# SMPS.net
KiCad netlist of a schematic drawn in Altium Designer
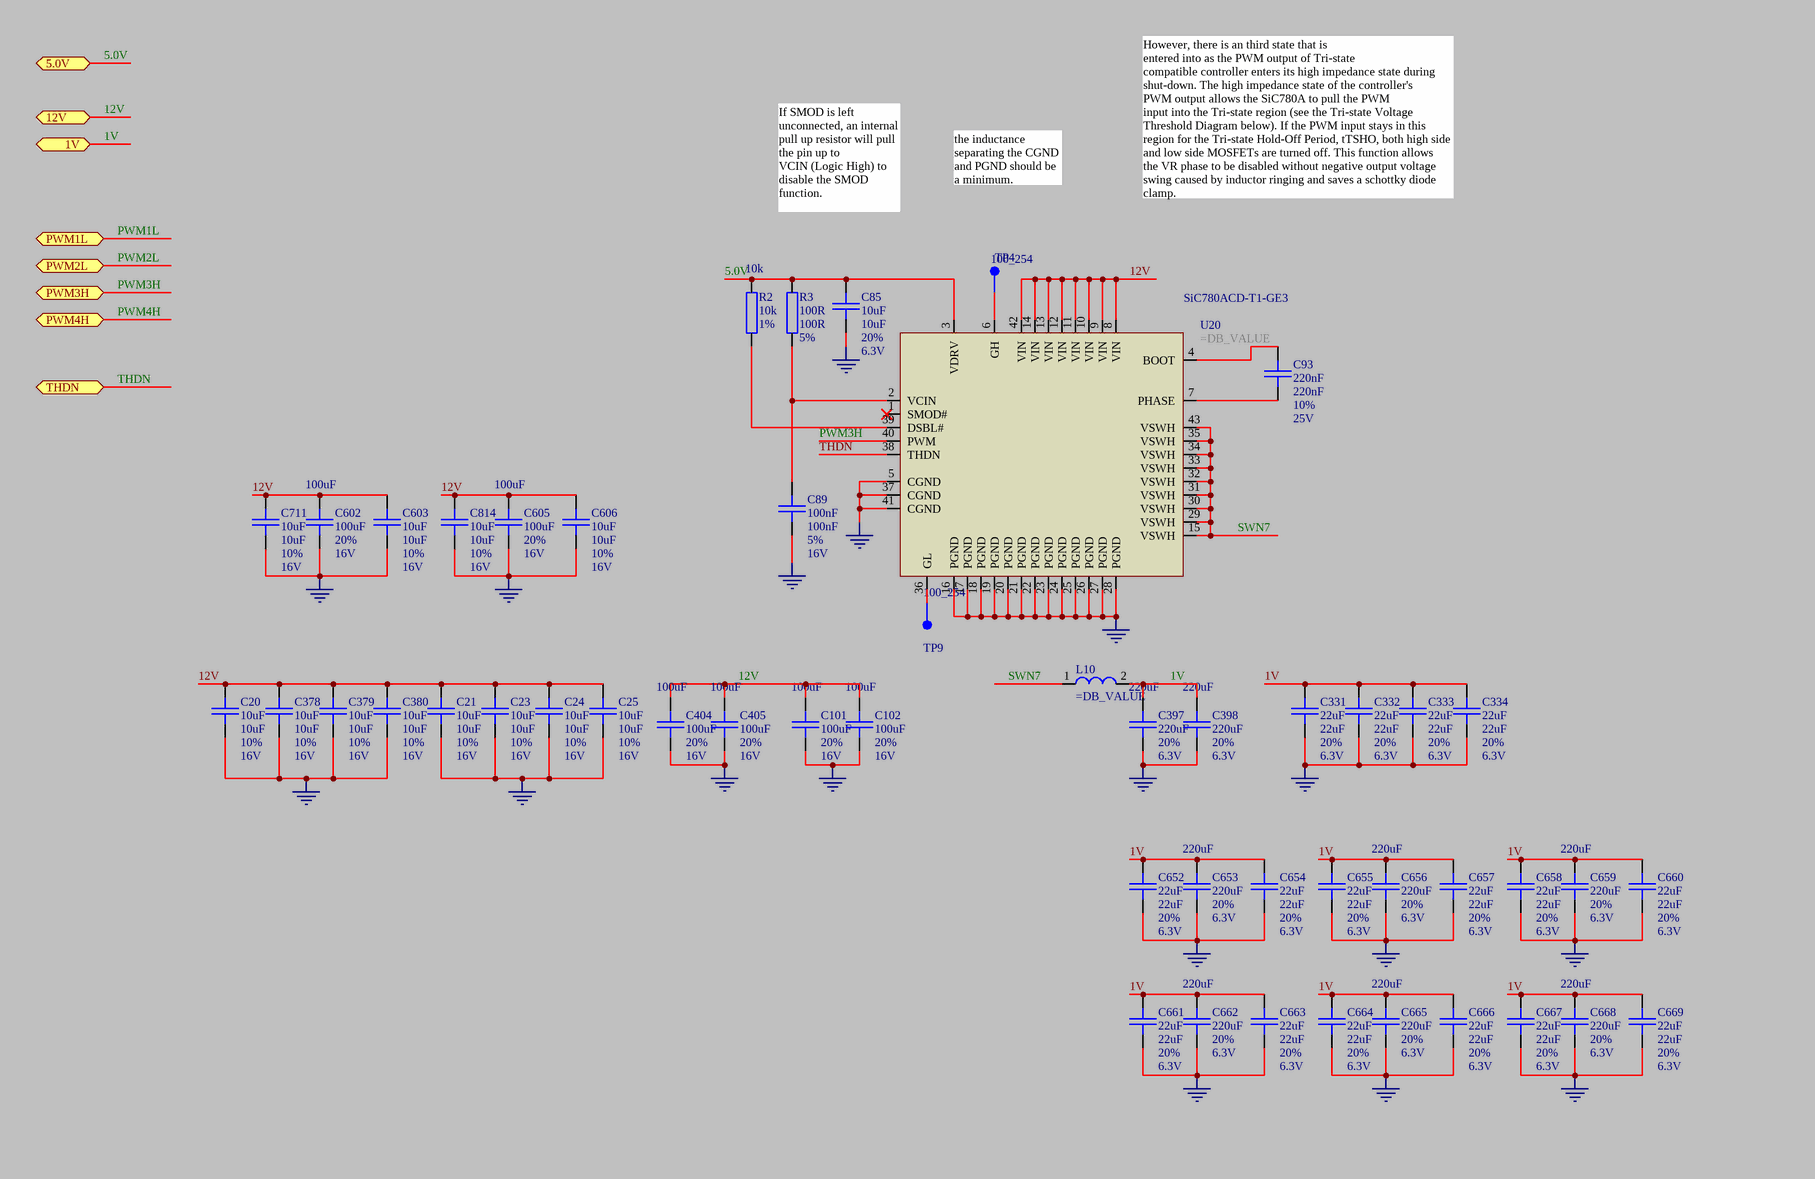
[diagram p0: SMPS.SchDoc, top left]
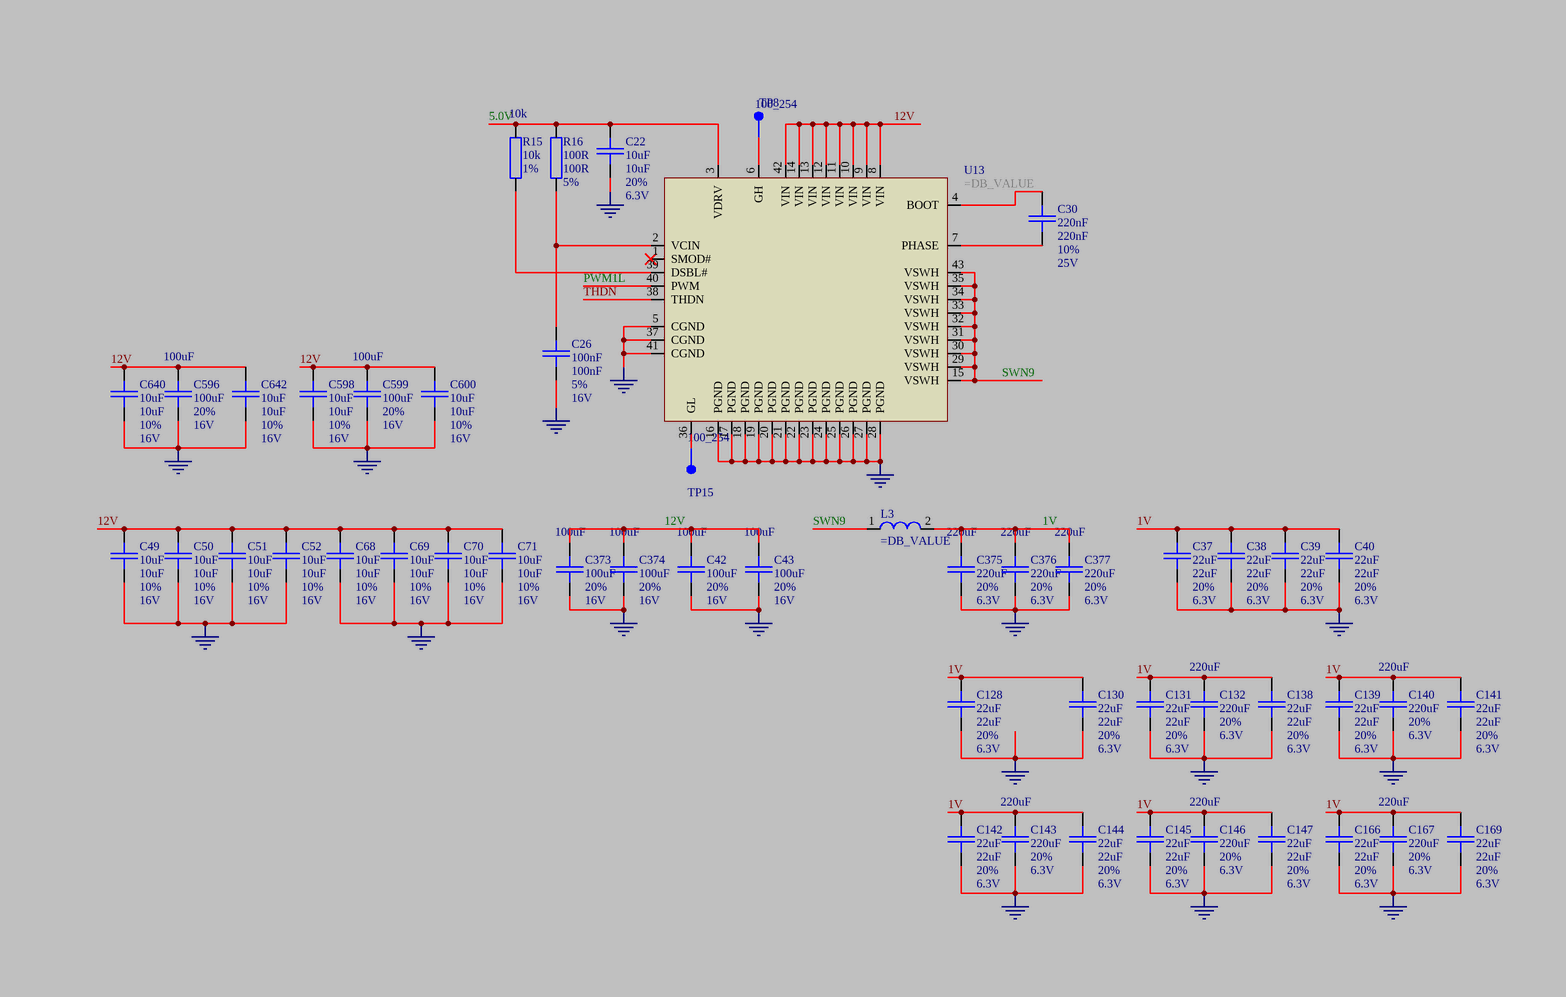
[diagram p1: SMPS.SchDoc, top right]
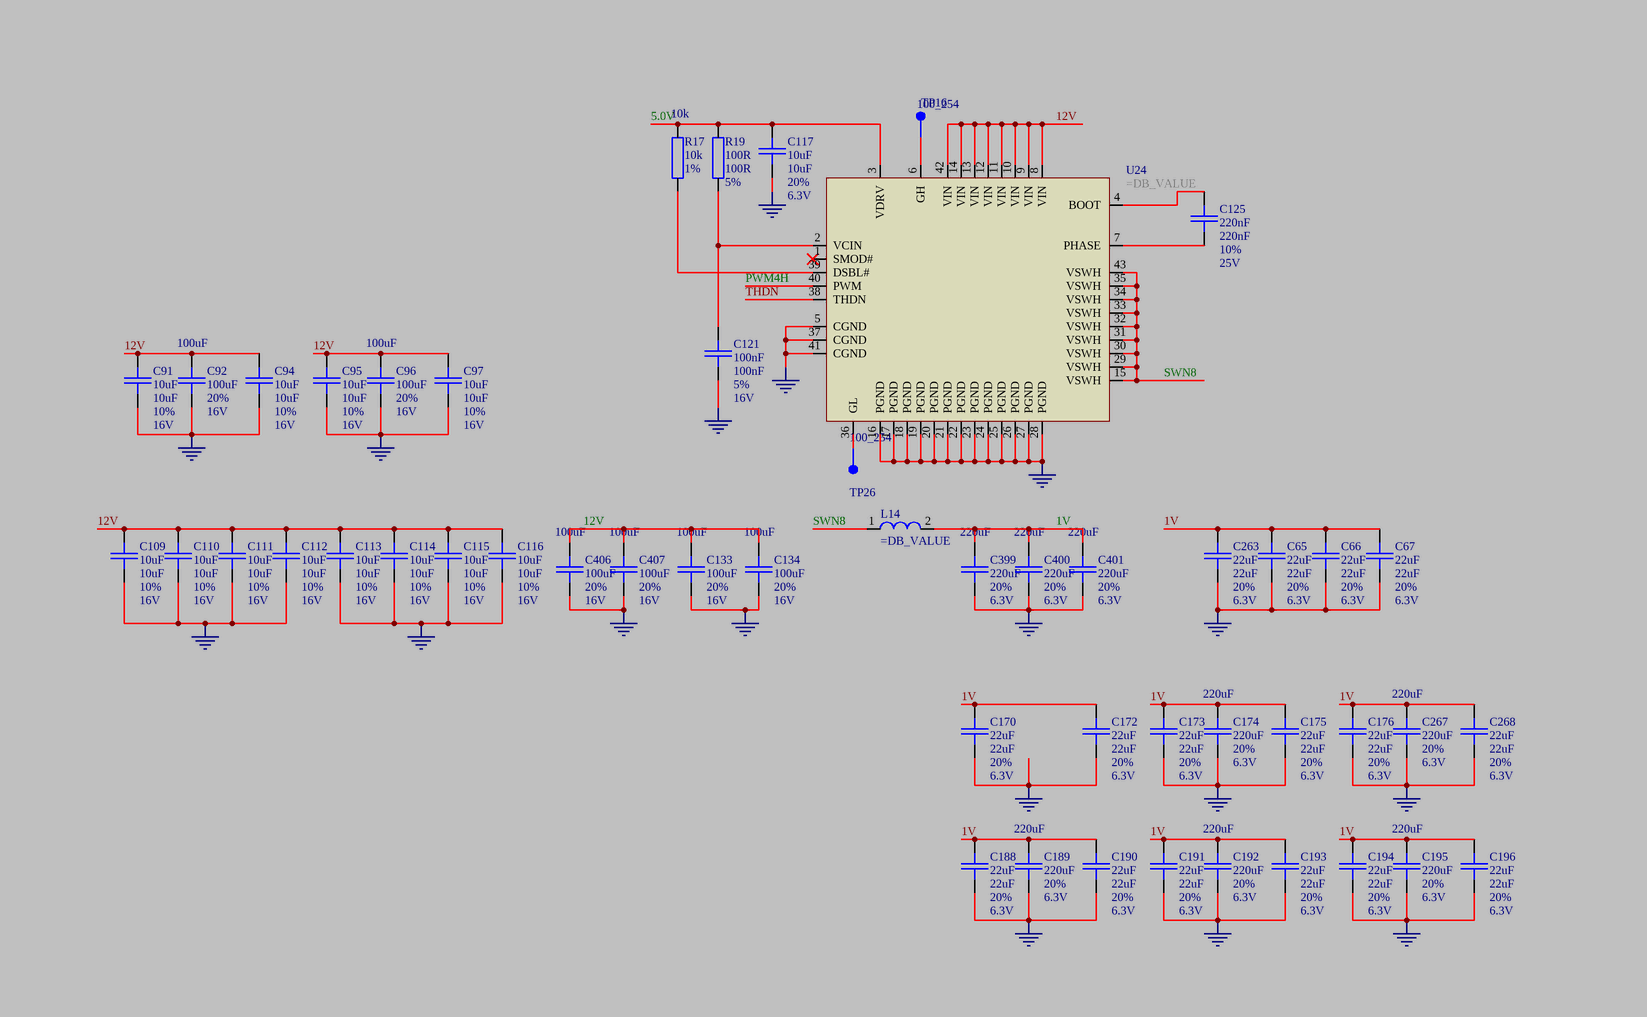
[diagram p2: SMPS.SchDoc, bottom left]
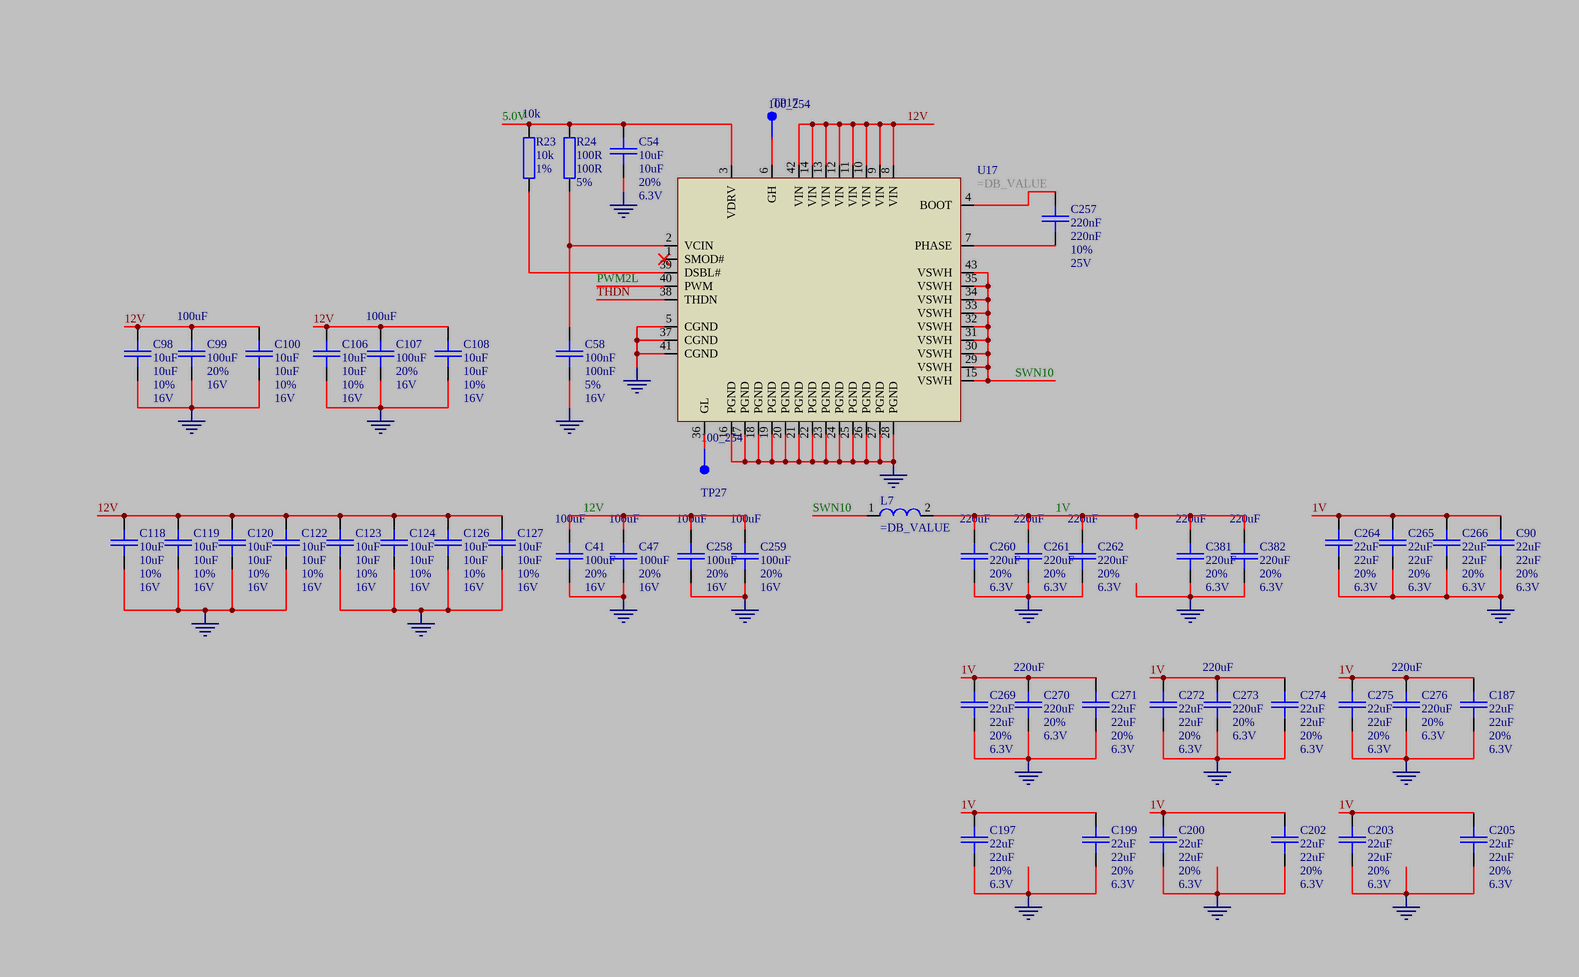
[diagram p3: SMPS.SchDoc, bottom right]

(export (version "E")
  (design (tool "Eeschema 10.0.6"))
  (components
    (comp (ref "C20")
      (value "10uF")
      (footprint "SMD_0805_CAPC2012X145N")
      (fields
        (field (name "DB_PART_NUMBER") "CAP000043636")
        (field (name "DB_VALUE") "10uF")
        (field (name "DB_TOLERANCE") "10%")
        (field (name "DB_VOLTAGE") "16V")
        (field (name "DB_MANUFACTURER_PART") "KEMET    C0805C106K4PAC")
        (field (name "DB_APPROVED_BY") "ISHIDDEN=T")
      )
      (libsource (lib "Database_Libs1") (part "C"))
    )
    (comp (ref "C21")
      (value "10uF")
      (footprint "SMD_0805_CAPC2012X145N")
      (fields
        (field (name "DB_PART_NUMBER") "CAP000043636")
        (field (name "DB_VALUE") "10uF")
        (field (name "DB_TOLERANCE") "10%")
        (field (name "DB_VOLTAGE") "16V")
        (field (name "DB_MANUFACTURER_PART") "KEMET    C0805C106K4PAC")
        (field (name "DB_APPROVED_BY") "ISHIDDEN=T")
      )
      (libsource (lib "Database_Libs1") (part "C"))
    )
    (comp (ref "C22")
      (value "10uF")
      (footprint "SMD_0603_CAPC1608X95N")
      (fields
        (field (name "DB_PART_NUMBER") "CAP000043646")
        (field (name "DB_VALUE") "10uF")
        (field (name "DB_TOLERANCE") "20%")
        (field (name "DB_VOLTAGE") "6.3V")
        (field (name "DB_MANUFACTURER_PART") "KEMET    C0603C106M9PAC")
        (field (name "DB_APPROVED_BY") "ISHIDDEN=T")
      )
      (libsource (lib "Database_Libs1") (part "C"))
    )
    (comp (ref "C23")
      (value "10uF")
      (footprint "SMD_0805_CAPC2012X145N")
      (fields
        (field (name "DB_PART_NUMBER") "CAP000043636")
        (field (name "DB_VALUE") "10uF")
        (field (name "DB_TOLERANCE") "10%")
        (field (name "DB_VOLTAGE") "16V")
        (field (name "DB_MANUFACTURER_PART") "KEMET    C0805C106K4PAC")
        (field (name "DB_APPROVED_BY") "ISHIDDEN=T")
      )
      (libsource (lib "Database_Libs1") (part "C"))
    )
    (comp (ref "C24")
      (value "10uF")
      (footprint "SMD_0805_CAPC2012X145N")
      (fields
        (field (name "DB_PART_NUMBER") "CAP000043636")
        (field (name "DB_VALUE") "10uF")
        (field (name "DB_TOLERANCE") "10%")
        (field (name "DB_VOLTAGE") "16V")
        (field (name "DB_MANUFACTURER_PART") "KEMET    C0805C106K4PAC")
        (field (name "DB_APPROVED_BY") "ISHIDDEN=T")
      )
      (libsource (lib "Database_Libs1") (part "C"))
    )
    (comp (ref "C25")
      (value "10uF")
      (footprint "SMD_0805_CAPC2012X145N")
      (fields
        (field (name "DB_PART_NUMBER") "CAP000043636")
        (field (name "DB_VALUE") "10uF")
        (field (name "DB_TOLERANCE") "10%")
        (field (name "DB_VOLTAGE") "16V")
        (field (name "DB_MANUFACTURER_PART") "KEMET    C0805C106K4PAC")
        (field (name "DB_APPROVED_BY") "ISHIDDEN=T")
      )
      (libsource (lib "Database_Libs1") (part "C"))
    )
    (comp (ref "C26")
      (value "100nF")
      (footprint "SMD_0603_CAPC1608X95N")
      (fields
        (field (name "DB_PART_NUMBER") "CAP000022706")
        (field (name "DB_VALUE") "100nF")
        (field (name "DB_TOLERANCE") "5%")
        (field (name "DB_VOLTAGE") "16V")
        (field (name "DB_MANUFACTURER_PART") "KEMET    C0603F104J4RAC")
        (field (name "DB_APPROVED_BY") "ISHIDDEN=T")
      )
      (libsource (lib "Database_Libs1") (part "C"))
    )
    (comp (ref "C30")
      (value "220nF")
      (footprint "SMD_0603_CAPC1608X95N")
      (fields
        (field (name "DB_PART_NUMBER") "CAP000022968")
        (field (name "DB_VALUE") "220nF")
        (field (name "DB_TOLERANCE") "10%")
        (field (name "DB_VOLTAGE") "25V")
        (field (name "DB_MANUFACTURER_PART") "KEMET    C0603F224K3RAC")
        (field (name "DB_APPROVED_BY") "ISHIDDEN=T")
      )
      (libsource (lib "Database_Libs1") (part "C"))
    )
    (comp (ref "C37")
      (value "22uF")
      (footprint "SMD_0805_CAPC2012X145N")
      (fields
        (field (name "DB_PART_NUMBER") "CAP000043686")
        (field (name "DB_VALUE") "22uF")
        (field (name "DB_TOLERANCE") "20%")
        (field (name "DB_VOLTAGE") "6.3V")
        (field (name "DB_MANUFACTURER_PART") "KEMET    C0805C226M9PAC")
        (field (name "DB_APPROVED_BY") "ISHIDDEN=T")
      )
      (libsource (lib "Database_Libs1") (part "C"))
    )
    (comp (ref "C38")
      (value "22uF")
      (footprint "SMD_0805_CAPC2012X145N")
      (fields
        (field (name "DB_PART_NUMBER") "CAP000043686")
        (field (name "DB_VALUE") "22uF")
        (field (name "DB_TOLERANCE") "20%")
        (field (name "DB_VOLTAGE") "6.3V")
        (field (name "DB_MANUFACTURER_PART") "KEMET    C0805C226M9PAC")
        (field (name "DB_APPROVED_BY") "ISHIDDEN=T")
      )
      (libsource (lib "Database_Libs1") (part "C"))
    )
    (comp (ref "C39")
      (value "22uF")
      (footprint "SMD_0805_CAPC2012X145N")
      (fields
        (field (name "DB_PART_NUMBER") "CAP000043686")
        (field (name "DB_VALUE") "22uF")
        (field (name "DB_TOLERANCE") "20%")
        (field (name "DB_VOLTAGE") "6.3V")
        (field (name "DB_MANUFACTURER_PART") "KEMET    C0805C226M9PAC")
        (field (name "DB_APPROVED_BY") "ISHIDDEN=T")
      )
      (libsource (lib "Database_Libs1") (part "C"))
    )
    (comp (ref "C40")
      (value "22uF")
      (footprint "SMD_0805_CAPC2012X145N")
      (fields
        (field (name "DB_PART_NUMBER") "CAP000043686")
        (field (name "DB_VALUE") "22uF")
        (field (name "DB_TOLERANCE") "20%")
        (field (name "DB_VOLTAGE") "6.3V")
        (field (name "DB_MANUFACTURER_PART") "KEMET    C0805C226M9PAC")
        (field (name "DB_APPROVED_BY") "ISHIDDEN=T")
      )
      (libsource (lib "Database_Libs1") (part "C"))
    )
    (comp (ref "C41")
      (value "100uF")
      (footprint "SMD_1210_CAPC3225X270N")
      (fields
        (field (name "DB_PART_NUMBER") "TMP-2512")
        (field (name "DB_VALUE") "100uF")
        (field (name "DB_TOLERANCE") "20%")
        (field (name "DB_VOLTAGE") "16V")
        (field (name "DB_MANUFACTURER_PART") "YAGEO    CC1210MRX5R7BB107")
      )
      (libsource (lib "Database_Libs1") (part "C"))
    )
    (comp (ref "C42")
      (value "100uF")
      (footprint "SMD_1210_CAPC3225X270N")
      (fields
        (field (name "DB_PART_NUMBER") "TMP-2512")
        (field (name "DB_VALUE") "100uF")
        (field (name "DB_TOLERANCE") "20%")
        (field (name "DB_VOLTAGE") "16V")
        (field (name "DB_MANUFACTURER_PART") "YAGEO    CC1210MRX5R7BB107")
      )
      (libsource (lib "Database_Libs1") (part "C"))
    )
    (comp (ref "C43")
      (value "100uF")
      (footprint "SMD_1210_CAPC3225X270N")
      (fields
        (field (name "DB_PART_NUMBER") "TMP-2512")
        (field (name "DB_VALUE") "100uF")
        (field (name "DB_TOLERANCE") "20%")
        (field (name "DB_VOLTAGE") "16V")
        (field (name "DB_MANUFACTURER_PART") "YAGEO    CC1210MRX5R7BB107")
      )
      (libsource (lib "Database_Libs1") (part "C"))
    )
    (comp (ref "C47")
      (value "100uF")
      (footprint "SMD_1210_CAPC3225X270N")
      (fields
        (field (name "DB_PART_NUMBER") "TMP-2512")
        (field (name "DB_VALUE") "100uF")
        (field (name "DB_TOLERANCE") "20%")
        (field (name "DB_VOLTAGE") "16V")
        (field (name "DB_MANUFACTURER_PART") "YAGEO    CC1210MRX5R7BB107")
      )
      (libsource (lib "Database_Libs1") (part "C"))
    )
    (comp (ref "C49")
      (value "10uF")
      (footprint "SMD_0805_CAPC2012X145N")
      (fields
        (field (name "DB_PART_NUMBER") "CAP000043636")
        (field (name "DB_VALUE") "10uF")
        (field (name "DB_TOLERANCE") "10%")
        (field (name "DB_VOLTAGE") "16V")
        (field (name "DB_MANUFACTURER_PART") "KEMET    C0805C106K4PAC")
        (field (name "DB_APPROVED_BY") "ISHIDDEN=T")
      )
      (libsource (lib "Database_Libs1") (part "C"))
    )
    (comp (ref "C50")
      (value "10uF")
      (footprint "SMD_0805_CAPC2012X145N")
      (fields
        (field (name "DB_PART_NUMBER") "CAP000043636")
        (field (name "DB_VALUE") "10uF")
        (field (name "DB_TOLERANCE") "10%")
        (field (name "DB_VOLTAGE") "16V")
        (field (name "DB_MANUFACTURER_PART") "KEMET    C0805C106K4PAC")
        (field (name "DB_APPROVED_BY") "ISHIDDEN=T")
      )
      (libsource (lib "Database_Libs1") (part "C"))
    )
    (comp (ref "C51")
      (value "10uF")
      (footprint "SMD_0805_CAPC2012X145N")
      (fields
        (field (name "DB_PART_NUMBER") "CAP000043636")
        (field (name "DB_VALUE") "10uF")
        (field (name "DB_TOLERANCE") "10%")
        (field (name "DB_VOLTAGE") "16V")
        (field (name "DB_MANUFACTURER_PART") "KEMET    C0805C106K4PAC")
        (field (name "DB_APPROVED_BY") "ISHIDDEN=T")
      )
      (libsource (lib "Database_Libs1") (part "C"))
    )
    (comp (ref "C52")
      (value "10uF")
      (footprint "SMD_0805_CAPC2012X145N")
      (fields
        (field (name "DB_PART_NUMBER") "CAP000043636")
        (field (name "DB_VALUE") "10uF")
        (field (name "DB_TOLERANCE") "10%")
        (field (name "DB_VOLTAGE") "16V")
        (field (name "DB_MANUFACTURER_PART") "KEMET    C0805C106K4PAC")
        (field (name "DB_APPROVED_BY") "ISHIDDEN=T")
      )
      (libsource (lib "Database_Libs1") (part "C"))
    )
    (comp (ref "C54")
      (value "10uF")
      (footprint "SMD_0603_CAPC1608X95N")
      (fields
        (field (name "DB_PART_NUMBER") "CAP000043646")
        (field (name "DB_VALUE") "10uF")
        (field (name "DB_TOLERANCE") "20%")
        (field (name "DB_VOLTAGE") "6.3V")
        (field (name "DB_MANUFACTURER_PART") "KEMET    C0603C106M9PAC")
        (field (name "DB_APPROVED_BY") "ISHIDDEN=T")
      )
      (libsource (lib "Database_Libs1") (part "C"))
    )
    (comp (ref "C58")
      (value "100nF")
      (footprint "SMD_0603_CAPC1608X95N")
      (fields
        (field (name "DB_PART_NUMBER") "CAP000022706")
        (field (name "DB_VALUE") "100nF")
        (field (name "DB_TOLERANCE") "5%")
        (field (name "DB_VOLTAGE") "16V")
        (field (name "DB_MANUFACTURER_PART") "KEMET    C0603F104J4RAC")
        (field (name "DB_APPROVED_BY") "ISHIDDEN=T")
      )
      (libsource (lib "Database_Libs1") (part "C"))
    )
    (comp (ref "C65")
      (value "22uF")
      (footprint "SMD_0805_CAPC2012X145N")
      (fields
        (field (name "DB_PART_NUMBER") "CAP000043686")
        (field (name "DB_VALUE") "22uF")
        (field (name "DB_TOLERANCE") "20%")
        (field (name "DB_VOLTAGE") "6.3V")
        (field (name "DB_MANUFACTURER_PART") "KEMET    C0805C226M9PAC")
        (field (name "DB_APPROVED_BY") "ISHIDDEN=T")
      )
      (libsource (lib "Database_Libs1") (part "C"))
    )
    (comp (ref "C66")
      (value "22uF")
      (footprint "SMD_0805_CAPC2012X145N")
      (fields
        (field (name "DB_PART_NUMBER") "CAP000043686")
        (field (name "DB_VALUE") "22uF")
        (field (name "DB_TOLERANCE") "20%")
        (field (name "DB_VOLTAGE") "6.3V")
        (field (name "DB_MANUFACTURER_PART") "KEMET    C0805C226M9PAC")
        (field (name "DB_APPROVED_BY") "ISHIDDEN=T")
      )
      (libsource (lib "Database_Libs1") (part "C"))
    )
    (comp (ref "C67")
      (value "22uF")
      (footprint "SMD_0805_CAPC2012X145N")
      (fields
        (field (name "DB_PART_NUMBER") "CAP000043686")
        (field (name "DB_VALUE") "22uF")
        (field (name "DB_TOLERANCE") "20%")
        (field (name "DB_VOLTAGE") "6.3V")
        (field (name "DB_MANUFACTURER_PART") "KEMET    C0805C226M9PAC")
        (field (name "DB_APPROVED_BY") "ISHIDDEN=T")
      )
      (libsource (lib "Database_Libs1") (part "C"))
    )
    (comp (ref "C68")
      (value "10uF")
      (footprint "SMD_0805_CAPC2012X145N")
      (fields
        (field (name "DB_PART_NUMBER") "CAP000043636")
        (field (name "DB_VALUE") "10uF")
        (field (name "DB_TOLERANCE") "10%")
        (field (name "DB_VOLTAGE") "16V")
        (field (name "DB_MANUFACTURER_PART") "KEMET    C0805C106K4PAC")
        (field (name "DB_APPROVED_BY") "ISHIDDEN=T")
      )
      (libsource (lib "Database_Libs1") (part "C"))
    )
    (comp (ref "C69")
      (value "10uF")
      (footprint "SMD_0805_CAPC2012X145N")
      (fields
        (field (name "DB_PART_NUMBER") "CAP000043636")
        (field (name "DB_VALUE") "10uF")
        (field (name "DB_TOLERANCE") "10%")
        (field (name "DB_VOLTAGE") "16V")
        (field (name "DB_MANUFACTURER_PART") "KEMET    C0805C106K4PAC")
        (field (name "DB_APPROVED_BY") "ISHIDDEN=T")
      )
      (libsource (lib "Database_Libs1") (part "C"))
    )
    (comp (ref "C70")
      (value "10uF")
      (footprint "SMD_0805_CAPC2012X145N")
      (fields
        (field (name "DB_PART_NUMBER") "CAP000043636")
        (field (name "DB_VALUE") "10uF")
        (field (name "DB_TOLERANCE") "10%")
        (field (name "DB_VOLTAGE") "16V")
        (field (name "DB_MANUFACTURER_PART") "KEMET    C0805C106K4PAC")
        (field (name "DB_APPROVED_BY") "ISHIDDEN=T")
      )
      (libsource (lib "Database_Libs1") (part "C"))
    )
    (comp (ref "C71")
      (value "10uF")
      (footprint "SMD_0805_CAPC2012X145N")
      (fields
        (field (name "DB_PART_NUMBER") "CAP000043636")
        (field (name "DB_VALUE") "10uF")
        (field (name "DB_TOLERANCE") "10%")
        (field (name "DB_VOLTAGE") "16V")
        (field (name "DB_MANUFACTURER_PART") "KEMET    C0805C106K4PAC")
        (field (name "DB_APPROVED_BY") "ISHIDDEN=T")
      )
      (libsource (lib "Database_Libs1") (part "C"))
    )
    (comp (ref "C85")
      (value "10uF")
      (footprint "SMD_0603_CAPC1608X95N")
      (fields
        (field (name "DB_PART_NUMBER") "CAP000043646")
        (field (name "DB_VALUE") "10uF")
        (field (name "DB_TOLERANCE") "20%")
        (field (name "DB_VOLTAGE") "6.3V")
        (field (name "DB_MANUFACTURER_PART") "KEMET    C0603C106M9PAC")
        (field (name "DB_APPROVED_BY") "ISHIDDEN=T")
      )
      (libsource (lib "Database_Libs1") (part "C"))
    )
    (comp (ref "C89")
      (value "100nF")
      (footprint "SMD_0603_CAPC1608X95N")
      (fields
        (field (name "DB_PART_NUMBER") "CAP000022706")
        (field (name "DB_VALUE") "100nF")
        (field (name "DB_TOLERANCE") "5%")
        (field (name "DB_VOLTAGE") "16V")
        (field (name "DB_MANUFACTURER_PART") "KEMET    C0603F104J4RAC")
        (field (name "DB_APPROVED_BY") "ISHIDDEN=T")
      )
      (libsource (lib "Database_Libs1") (part "C"))
    )
    (comp (ref "C90")
      (value "22uF")
      (footprint "SMD_0805_CAPC2012X145N")
      (fields
        (field (name "DB_PART_NUMBER") "CAP000043686")
        (field (name "DB_VALUE") "22uF")
        (field (name "DB_TOLERANCE") "20%")
        (field (name "DB_VOLTAGE") "6.3V")
        (field (name "DB_MANUFACTURER_PART") "KEMET    C0805C226M9PAC")
        (field (name "DB_APPROVED_BY") "ISHIDDEN=T")
      )
      (libsource (lib "Database_Libs1") (part "C"))
    )
    (comp (ref "C91")
      (value "10uF")
      (footprint "SMD_0805_CAPC2012X145N")
      (fields
        (field (name "DB_PART_NUMBER") "CAP000043636")
        (field (name "DB_VALUE") "10uF")
        (field (name "DB_TOLERANCE") "10%")
        (field (name "DB_VOLTAGE") "16V")
        (field (name "DB_MANUFACTURER_PART") "KEMET    C0805C106K4PAC")
        (field (name "DB_APPROVED_BY") "ISHIDDEN=T")
      )
      (libsource (lib "Database_Libs1") (part "C"))
    )
    (comp (ref "C92")
      (value "100uF")
      (footprint "SMD_1210_CAPC3225X270N")
      (fields
        (field (name "DB_PART_NUMBER") "TMP-2512")
        (field (name "DB_VALUE") "100uF")
        (field (name "DB_TOLERANCE") "20%")
        (field (name "DB_VOLTAGE") "16V")
        (field (name "DB_MANUFACTURER_PART") "YAGEO    CC1210MRX5R7BB107")
      )
      (libsource (lib "Database_Libs1") (part "C"))
    )
    (comp (ref "C93")
      (value "220nF")
      (footprint "SMD_0603_CAPC1608X95N")
      (fields
        (field (name "DB_PART_NUMBER") "CAP000022968")
        (field (name "DB_VALUE") "220nF")
        (field (name "DB_TOLERANCE") "10%")
        (field (name "DB_VOLTAGE") "25V")
        (field (name "DB_MANUFACTURER_PART") "KEMET    C0603F224K3RAC")
        (field (name "DB_APPROVED_BY") "ISHIDDEN=T")
      )
      (libsource (lib "Database_Libs1") (part "C"))
    )
    (comp (ref "C94")
      (value "10uF")
      (footprint "SMD_0805_CAPC2012X145N")
      (fields
        (field (name "DB_PART_NUMBER") "CAP000043636")
        (field (name "DB_VALUE") "10uF")
        (field (name "DB_TOLERANCE") "10%")
        (field (name "DB_VOLTAGE") "16V")
        (field (name "DB_MANUFACTURER_PART") "KEMET    C0805C106K4PAC")
        (field (name "DB_APPROVED_BY") "ISHIDDEN=T")
      )
      (libsource (lib "Database_Libs1") (part "C"))
    )
    (comp (ref "C95")
      (value "10uF")
      (footprint "SMD_0805_CAPC2012X145N")
      (fields
        (field (name "DB_PART_NUMBER") "CAP000043636")
        (field (name "DB_VALUE") "10uF")
        (field (name "DB_TOLERANCE") "10%")
        (field (name "DB_VOLTAGE") "16V")
        (field (name "DB_MANUFACTURER_PART") "KEMET    C0805C106K4PAC")
        (field (name "DB_APPROVED_BY") "ISHIDDEN=T")
      )
      (libsource (lib "Database_Libs1") (part "C"))
    )
    (comp (ref "C96")
      (value "100uF")
      (footprint "SMD_1210_CAPC3225X270N")
      (fields
        (field (name "DB_PART_NUMBER") "TMP-2512")
        (field (name "DB_VALUE") "100uF")
        (field (name "DB_TOLERANCE") "20%")
        (field (name "DB_VOLTAGE") "16V")
        (field (name "DB_MANUFACTURER_PART") "YAGEO    CC1210MRX5R7BB107")
      )
      (libsource (lib "Database_Libs1") (part "C"))
    )
    (comp (ref "C97")
      (value "10uF")
      (footprint "SMD_0805_CAPC2012X145N")
      (fields
        (field (name "DB_PART_NUMBER") "CAP000043636")
        (field (name "DB_VALUE") "10uF")
        (field (name "DB_TOLERANCE") "10%")
        (field (name "DB_VOLTAGE") "16V")
        (field (name "DB_MANUFACTURER_PART") "KEMET    C0805C106K4PAC")
        (field (name "DB_APPROVED_BY") "ISHIDDEN=T")
      )
      (libsource (lib "Database_Libs1") (part "C"))
    )
    (comp (ref "C98")
      (value "10uF")
      (footprint "SMD_0805_CAPC2012X145N")
      (fields
        (field (name "DB_PART_NUMBER") "CAP000043636")
        (field (name "DB_VALUE") "10uF")
        (field (name "DB_TOLERANCE") "10%")
        (field (name "DB_VOLTAGE") "16V")
        (field (name "DB_MANUFACTURER_PART") "KEMET    C0805C106K4PAC")
        (field (name "DB_APPROVED_BY") "ISHIDDEN=T")
      )
      (libsource (lib "Database_Libs1") (part "C"))
    )
    (comp (ref "C99")
      (value "100uF")
      (footprint "SMD_1210_CAPC3225X270N")
      (fields
        (field (name "DB_PART_NUMBER") "TMP-2512")
        (field (name "DB_VALUE") "100uF")
        (field (name "DB_TOLERANCE") "20%")
        (field (name "DB_VOLTAGE") "16V")
        (field (name "DB_MANUFACTURER_PART") "YAGEO    CC1210MRX5R7BB107")
      )
      (libsource (lib "Database_Libs1") (part "C"))
    )
    (comp (ref "C100")
      (value "10uF")
      (footprint "SMD_0805_CAPC2012X145N")
      (fields
        (field (name "DB_PART_NUMBER") "CAP000043636")
        (field (name "DB_VALUE") "10uF")
        (field (name "DB_TOLERANCE") "10%")
        (field (name "DB_VOLTAGE") "16V")
        (field (name "DB_MANUFACTURER_PART") "KEMET    C0805C106K4PAC")
        (field (name "DB_APPROVED_BY") "ISHIDDEN=T")
      )
      (libsource (lib "Database_Libs1") (part "C"))
    )
    (comp (ref "C101")
      (value "100uF")
      (footprint "SMD_1210_CAPC3225X270N")
      (fields
        (field (name "DB_PART_NUMBER") "TMP-2512")
        (field (name "DB_VALUE") "100uF")
        (field (name "DB_TOLERANCE") "20%")
        (field (name "DB_VOLTAGE") "16V")
        (field (name "DB_MANUFACTURER_PART") "YAGEO    CC1210MRX5R7BB107")
      )
      (libsource (lib "Database_Libs1") (part "C"))
    )
    (comp (ref "C102")
      (value "100uF")
      (footprint "SMD_1210_CAPC3225X270N")
      (fields
        (field (name "DB_PART_NUMBER") "TMP-2512")
        (field (name "DB_VALUE") "100uF")
        (field (name "DB_TOLERANCE") "20%")
        (field (name "DB_VOLTAGE") "16V")
        (field (name "DB_MANUFACTURER_PART") "YAGEO    CC1210MRX5R7BB107")
      )
      (libsource (lib "Database_Libs1") (part "C"))
    )
    (comp (ref "C106")
      (value "10uF")
      (footprint "SMD_0805_CAPC2012X145N")
      (fields
        (field (name "DB_PART_NUMBER") "CAP000043636")
        (field (name "DB_VALUE") "10uF")
        (field (name "DB_TOLERANCE") "10%")
        (field (name "DB_VOLTAGE") "16V")
        (field (name "DB_MANUFACTURER_PART") "KEMET    C0805C106K4PAC")
        (field (name "DB_APPROVED_BY") "ISHIDDEN=T")
      )
      (libsource (lib "Database_Libs1") (part "C"))
    )
    (comp (ref "C107")
      (value "100uF")
      (footprint "SMD_1210_CAPC3225X270N")
      (fields
        (field (name "DB_PART_NUMBER") "TMP-2512")
        (field (name "DB_VALUE") "100uF")
        (field (name "DB_TOLERANCE") "20%")
        (field (name "DB_VOLTAGE") "16V")
        (field (name "DB_MANUFACTURER_PART") "YAGEO    CC1210MRX5R7BB107")
      )
      (libsource (lib "Database_Libs1") (part "C"))
    )
    (comp (ref "C108")
      (value "10uF")
      (footprint "SMD_0805_CAPC2012X145N")
      (fields
        (field (name "DB_PART_NUMBER") "CAP000043636")
        (field (name "DB_VALUE") "10uF")
        (field (name "DB_TOLERANCE") "10%")
        (field (name "DB_VOLTAGE") "16V")
        (field (name "DB_MANUFACTURER_PART") "KEMET    C0805C106K4PAC")
        (field (name "DB_APPROVED_BY") "ISHIDDEN=T")
      )
      (libsource (lib "Database_Libs1") (part "C"))
    )
    (comp (ref "C109")
      (value "10uF")
      (footprint "SMD_0805_CAPC2012X145N")
      (fields
        (field (name "DB_PART_NUMBER") "CAP000043636")
        (field (name "DB_VALUE") "10uF")
        (field (name "DB_TOLERANCE") "10%")
        (field (name "DB_VOLTAGE") "16V")
        (field (name "DB_MANUFACTURER_PART") "KEMET    C0805C106K4PAC")
        (field (name "DB_APPROVED_BY") "ISHIDDEN=T")
      )
      (libsource (lib "Database_Libs1") (part "C"))
    )
    (comp (ref "C110")
      (value "10uF")
      (footprint "SMD_0805_CAPC2012X145N")
      (fields
        (field (name "DB_PART_NUMBER") "CAP000043636")
        (field (name "DB_VALUE") "10uF")
        (field (name "DB_TOLERANCE") "10%")
        (field (name "DB_VOLTAGE") "16V")
        (field (name "DB_MANUFACTURER_PART") "KEMET    C0805C106K4PAC")
        (field (name "DB_APPROVED_BY") "ISHIDDEN=T")
      )
      (libsource (lib "Database_Libs1") (part "C"))
    )
    (comp (ref "C111")
      (value "10uF")
      (footprint "SMD_0805_CAPC2012X145N")
      (fields
        (field (name "DB_PART_NUMBER") "CAP000043636")
        (field (name "DB_VALUE") "10uF")
        (field (name "DB_TOLERANCE") "10%")
        (field (name "DB_VOLTAGE") "16V")
        (field (name "DB_MANUFACTURER_PART") "KEMET    C0805C106K4PAC")
        (field (name "DB_APPROVED_BY") "ISHIDDEN=T")
      )
      (libsource (lib "Database_Libs1") (part "C"))
    )
    (comp (ref "C112")
      (value "10uF")
      (footprint "SMD_0805_CAPC2012X145N")
      (fields
        (field (name "DB_PART_NUMBER") "CAP000043636")
        (field (name "DB_VALUE") "10uF")
        (field (name "DB_TOLERANCE") "10%")
        (field (name "DB_VOLTAGE") "16V")
        (field (name "DB_MANUFACTURER_PART") "KEMET    C0805C106K4PAC")
        (field (name "DB_APPROVED_BY") "ISHIDDEN=T")
      )
      (libsource (lib "Database_Libs1") (part "C"))
    )
    (comp (ref "C113")
      (value "10uF")
      (footprint "SMD_0805_CAPC2012X145N")
      (fields
        (field (name "DB_PART_NUMBER") "CAP000043636")
        (field (name "DB_VALUE") "10uF")
        (field (name "DB_TOLERANCE") "10%")
        (field (name "DB_VOLTAGE") "16V")
        (field (name "DB_MANUFACTURER_PART") "KEMET    C0805C106K4PAC")
        (field (name "DB_APPROVED_BY") "ISHIDDEN=T")
      )
      (libsource (lib "Database_Libs1") (part "C"))
    )
    (comp (ref "C114")
      (value "10uF")
      (footprint "SMD_0805_CAPC2012X145N")
      (fields
        (field (name "DB_PART_NUMBER") "CAP000043636")
        (field (name "DB_VALUE") "10uF")
        (field (name "DB_TOLERANCE") "10%")
        (field (name "DB_VOLTAGE") "16V")
        (field (name "DB_MANUFACTURER_PART") "KEMET    C0805C106K4PAC")
        (field (name "DB_APPROVED_BY") "ISHIDDEN=T")
      )
      (libsource (lib "Database_Libs1") (part "C"))
    )
    (comp (ref "C115")
      (value "10uF")
      (footprint "SMD_0805_CAPC2012X145N")
      (fields
        (field (name "DB_PART_NUMBER") "CAP000043636")
        (field (name "DB_VALUE") "10uF")
        (field (name "DB_TOLERANCE") "10%")
        (field (name "DB_VOLTAGE") "16V")
        (field (name "DB_MANUFACTURER_PART") "KEMET    C0805C106K4PAC")
        (field (name "DB_APPROVED_BY") "ISHIDDEN=T")
      )
      (libsource (lib "Database_Libs1") (part "C"))
    )
    (comp (ref "C116")
      (value "10uF")
      (footprint "SMD_0805_CAPC2012X145N")
      (fields
        (field (name "DB_PART_NUMBER") "CAP000043636")
        (field (name "DB_VALUE") "10uF")
        (field (name "DB_TOLERANCE") "10%")
        (field (name "DB_VOLTAGE") "16V")
        (field (name "DB_MANUFACTURER_PART") "KEMET    C0805C106K4PAC")
        (field (name "DB_APPROVED_BY") "ISHIDDEN=T")
      )
      (libsource (lib "Database_Libs1") (part "C"))
    )
    (comp (ref "C117")
      (value "10uF")
      (footprint "SMD_0603_CAPC1608X95N")
      (fields
        (field (name "DB_PART_NUMBER") "CAP000043646")
        (field (name "DB_VALUE") "10uF")
        (field (name "DB_TOLERANCE") "20%")
        (field (name "DB_VOLTAGE") "6.3V")
        (field (name "DB_MANUFACTURER_PART") "KEMET    C0603C106M9PAC")
        (field (name "DB_APPROVED_BY") "ISHIDDEN=T")
      )
      (libsource (lib "Database_Libs1") (part "C"))
    )
    (comp (ref "C118")
      (value "10uF")
      (footprint "SMD_0805_CAPC2012X145N")
      (fields
        (field (name "DB_PART_NUMBER") "CAP000043636")
        (field (name "DB_VALUE") "10uF")
        (field (name "DB_TOLERANCE") "10%")
        (field (name "DB_VOLTAGE") "16V")
        (field (name "DB_MANUFACTURER_PART") "KEMET    C0805C106K4PAC")
        (field (name "DB_APPROVED_BY") "ISHIDDEN=T")
      )
      (libsource (lib "Database_Libs1") (part "C"))
    )
    (comp (ref "C119")
      (value "10uF")
      (footprint "SMD_0805_CAPC2012X145N")
      (fields
        (field (name "DB_PART_NUMBER") "CAP000043636")
        (field (name "DB_VALUE") "10uF")
        (field (name "DB_TOLERANCE") "10%")
        (field (name "DB_VOLTAGE") "16V")
        (field (name "DB_MANUFACTURER_PART") "KEMET    C0805C106K4PAC")
        (field (name "DB_APPROVED_BY") "ISHIDDEN=T")
      )
      (libsource (lib "Database_Libs1") (part "C"))
    )
    (comp (ref "C120")
      (value "10uF")
      (footprint "SMD_0805_CAPC2012X145N")
      (fields
        (field (name "DB_PART_NUMBER") "CAP000043636")
        (field (name "DB_VALUE") "10uF")
        (field (name "DB_TOLERANCE") "10%")
        (field (name "DB_VOLTAGE") "16V")
        (field (name "DB_MANUFACTURER_PART") "KEMET    C0805C106K4PAC")
        (field (name "DB_APPROVED_BY") "ISHIDDEN=T")
      )
      (libsource (lib "Database_Libs1") (part "C"))
    )
    (comp (ref "C121")
      (value "100nF")
      (footprint "SMD_0603_CAPC1608X95N")
      (fields
        (field (name "DB_PART_NUMBER") "CAP000022706")
        (field (name "DB_VALUE") "100nF")
        (field (name "DB_TOLERANCE") "5%")
        (field (name "DB_VOLTAGE") "16V")
        (field (name "DB_MANUFACTURER_PART") "KEMET    C0603F104J4RAC")
        (field (name "DB_APPROVED_BY") "ISHIDDEN=T")
      )
      (libsource (lib "Database_Libs1") (part "C"))
    )
    (comp (ref "C122")
      (value "10uF")
      (footprint "SMD_0805_CAPC2012X145N")
      (fields
        (field (name "DB_PART_NUMBER") "CAP000043636")
        (field (name "DB_VALUE") "10uF")
        (field (name "DB_TOLERANCE") "10%")
        (field (name "DB_VOLTAGE") "16V")
        (field (name "DB_MANUFACTURER_PART") "KEMET    C0805C106K4PAC")
        (field (name "DB_APPROVED_BY") "ISHIDDEN=T")
      )
      (libsource (lib "Database_Libs1") (part "C"))
    )
    (comp (ref "C123")
      (value "10uF")
      (footprint "SMD_0805_CAPC2012X145N")
      (fields
        (field (name "DB_PART_NUMBER") "CAP000043636")
        (field (name "DB_VALUE") "10uF")
        (field (name "DB_TOLERANCE") "10%")
        (field (name "DB_VOLTAGE") "16V")
        (field (name "DB_MANUFACTURER_PART") "KEMET    C0805C106K4PAC")
        (field (name "DB_APPROVED_BY") "ISHIDDEN=T")
      )
      (libsource (lib "Database_Libs1") (part "C"))
    )
    (comp (ref "C124")
      (value "10uF")
      (footprint "SMD_0805_CAPC2012X145N")
      (fields
        (field (name "DB_PART_NUMBER") "CAP000043636")
        (field (name "DB_VALUE") "10uF")
        (field (name "DB_TOLERANCE") "10%")
        (field (name "DB_VOLTAGE") "16V")
        (field (name "DB_MANUFACTURER_PART") "KEMET    C0805C106K4PAC")
        (field (name "DB_APPROVED_BY") "ISHIDDEN=T")
      )
      (libsource (lib "Database_Libs1") (part "C"))
    )
    (comp (ref "C125")
      (value "220nF")
      (footprint "SMD_0603_CAPC1608X95N")
      (fields
        (field (name "DB_PART_NUMBER") "CAP000022968")
        (field (name "DB_VALUE") "220nF")
        (field (name "DB_TOLERANCE") "10%")
        (field (name "DB_VOLTAGE") "25V")
        (field (name "DB_MANUFACTURER_PART") "KEMET    C0603F224K3RAC")
        (field (name "DB_APPROVED_BY") "ISHIDDEN=T")
      )
      (libsource (lib "Database_Libs1") (part "C"))
    )
    (comp (ref "C126")
      (value "10uF")
      (footprint "SMD_0805_CAPC2012X145N")
      (fields
        (field (name "DB_PART_NUMBER") "CAP000043636")
        (field (name "DB_VALUE") "10uF")
        (field (name "DB_TOLERANCE") "10%")
        (field (name "DB_VOLTAGE") "16V")
        (field (name "DB_MANUFACTURER_PART") "KEMET    C0805C106K4PAC")
        (field (name "DB_APPROVED_BY") "ISHIDDEN=T")
      )
      (libsource (lib "Database_Libs1") (part "C"))
    )
    (comp (ref "C127")
      (value "10uF")
      (footprint "SMD_0805_CAPC2012X145N")
      (fields
        (field (name "DB_PART_NUMBER") "CAP000043636")
        (field (name "DB_VALUE") "10uF")
        (field (name "DB_TOLERANCE") "10%")
        (field (name "DB_VOLTAGE") "16V")
        (field (name "DB_MANUFACTURER_PART") "KEMET    C0805C106K4PAC")
        (field (name "DB_APPROVED_BY") "ISHIDDEN=T")
      )
      (libsource (lib "Database_Libs1") (part "C"))
    )
    (comp (ref "C128")
      (value "22uF")
      (footprint "SMD_0805_CAPC2012X145N")
      (fields
        (field (name "DB_PART_NUMBER") "CAP000043686")
        (field (name "DB_VALUE") "22uF")
        (field (name "DB_TOLERANCE") "20%")
        (field (name "DB_VOLTAGE") "6.3V")
        (field (name "DB_MANUFACTURER_PART") "KEMET    C0805C226M9PAC")
        (field (name "DB_APPROVED_BY") "ISHIDDEN=T")
      )
      (libsource (lib "Database_Libs1") (part "C"))
    )
    (comp (ref "C130")
      (value "22uF")
      (footprint "SMD_0805_CAPC2012X145N")
      (fields
        (field (name "DB_PART_NUMBER") "CAP000043686")
        (field (name "DB_VALUE") "22uF")
        (field (name "DB_TOLERANCE") "20%")
        (field (name "DB_VOLTAGE") "6.3V")
        (field (name "DB_MANUFACTURER_PART") "KEMET    C0805C226M9PAC")
        (field (name "DB_APPROVED_BY") "ISHIDDEN=T")
      )
      (libsource (lib "Database_Libs1") (part "C"))
    )
    (comp (ref "C131")
      (value "22uF")
      (footprint "SMD_0805_CAPC2012X145N")
      (fields
        (field (name "DB_PART_NUMBER") "CAP000043686")
        (field (name "DB_VALUE") "22uF")
        (field (name "DB_TOLERANCE") "20%")
        (field (name "DB_VOLTAGE") "6.3V")
        (field (name "DB_MANUFACTURER_PART") "KEMET    C0805C226M9PAC")
        (field (name "DB_APPROVED_BY") "ISHIDDEN=T")
      )
      (libsource (lib "Database_Libs1") (part "C"))
    )
    (comp (ref "C132")
      (value "220uF")
      (footprint "SMD_1210_CAPC3225X279N")
      (fields
        (field (name "DB_PART_NUMBER") "CAP000047355")
        (field (name "DB_VALUE") "220uF")
        (field (name "DB_TOLERANCE") "20%")
        (field (name "DB_VOLTAGE") "6.3V")
        (field (name "DB_MANUFACTURER_PART") "SAMSUNG    CL32A227MQVNNNE")
        (field (name "DB_APPROVED_BY") "VSN")
      )
      (libsource (lib "Database_Libs1") (part "C"))
    )
    (comp (ref "C133")
      (value "100uF")
      (footprint "SMD_1210_CAPC3225X270N")
      (fields
        (field (name "DB_PART_NUMBER") "TMP-2512")
        (field (name "DB_VALUE") "100uF")
        (field (name "DB_TOLERANCE") "20%")
        (field (name "DB_VOLTAGE") "16V")
        (field (name "DB_MANUFACTURER_PART") "YAGEO    CC1210MRX5R7BB107")
      )
      (libsource (lib "Database_Libs1") (part "C"))
    )
    (comp (ref "C134")
      (value "100uF")
      (footprint "SMD_1210_CAPC3225X270N")
      (fields
        (field (name "DB_PART_NUMBER") "TMP-2512")
        (field (name "DB_VALUE") "100uF")
        (field (name "DB_TOLERANCE") "20%")
        (field (name "DB_VOLTAGE") "16V")
        (field (name "DB_MANUFACTURER_PART") "YAGEO    CC1210MRX5R7BB107")
      )
      (libsource (lib "Database_Libs1") (part "C"))
    )
    (comp (ref "C138")
      (value "22uF")
      (footprint "SMD_0805_CAPC2012X145N")
      (fields
        (field (name "DB_PART_NUMBER") "CAP000043686")
        (field (name "DB_VALUE") "22uF")
        (field (name "DB_TOLERANCE") "20%")
        (field (name "DB_VOLTAGE") "6.3V")
        (field (name "DB_MANUFACTURER_PART") "KEMET    C0805C226M9PAC")
        (field (name "DB_APPROVED_BY") "ISHIDDEN=T")
      )
      (libsource (lib "Database_Libs1") (part "C"))
    )
    (comp (ref "C139")
      (value "22uF")
      (footprint "SMD_0805_CAPC2012X145N")
      (fields
        (field (name "DB_PART_NUMBER") "CAP000043686")
        (field (name "DB_VALUE") "22uF")
        (field (name "DB_TOLERANCE") "20%")
        (field (name "DB_VOLTAGE") "6.3V")
        (field (name "DB_MANUFACTURER_PART") "KEMET    C0805C226M9PAC")
        (field (name "DB_APPROVED_BY") "ISHIDDEN=T")
      )
      (libsource (lib "Database_Libs1") (part "C"))
    )
    (comp (ref "C140")
      (value "220uF")
      (footprint "SMD_1210_CAPC3225X279N")
      (fields
        (field (name "DB_PART_NUMBER") "CAP000047355")
        (field (name "DB_VALUE") "220uF")
        (field (name "DB_TOLERANCE") "20%")
        (field (name "DB_VOLTAGE") "6.3V")
        (field (name "DB_MANUFACTURER_PART") "SAMSUNG    CL32A227MQVNNNE")
        (field (name "DB_APPROVED_BY") "VSN")
      )
      (libsource (lib "Database_Libs1") (part "C"))
    )
    (comp (ref "C141")
      (value "22uF")
      (footprint "SMD_0805_CAPC2012X145N")
      (fields
        (field (name "DB_PART_NUMBER") "CAP000043686")
        (field (name "DB_VALUE") "22uF")
        (field (name "DB_TOLERANCE") "20%")
        (field (name "DB_VOLTAGE") "6.3V")
        (field (name "DB_MANUFACTURER_PART") "KEMET    C0805C226M9PAC")
        (field (name "DB_APPROVED_BY") "ISHIDDEN=T")
      )
      (libsource (lib "Database_Libs1") (part "C"))
    )
    (comp (ref "C142")
      (value "22uF")
      (footprint "SMD_0805_CAPC2012X145N")
      (fields
        (field (name "DB_PART_NUMBER") "CAP000043686")
        (field (name "DB_VALUE") "22uF")
        (field (name "DB_TOLERANCE") "20%")
        (field (name "DB_VOLTAGE") "6.3V")
        (field (name "DB_MANUFACTURER_PART") "KEMET    C0805C226M9PAC")
        (field (name "DB_APPROVED_BY") "ISHIDDEN=T")
      )
      (libsource (lib "Database_Libs1") (part "C"))
    )
    (comp (ref "C143")
      (value "220uF")
      (footprint "SMD_1210_CAPC3225X279N")
      (fields
        (field (name "DB_PART_NUMBER") "CAP000047355")
        (field (name "DB_VALUE") "220uF")
        (field (name "DB_TOLERANCE") "20%")
        (field (name "DB_VOLTAGE") "6.3V")
        (field (name "DB_MANUFACTURER_PART") "SAMSUNG    CL32A227MQVNNNE")
        (field (name "DB_APPROVED_BY") "VSN")
      )
      (libsource (lib "Database_Libs1") (part "C"))
    )
    (comp (ref "C144")
      (value "22uF")
      (footprint "SMD_0805_CAPC2012X145N")
      (fields
        (field (name "DB_PART_NUMBER") "CAP000043686")
        (field (name "DB_VALUE") "22uF")
        (field (name "DB_TOLERANCE") "20%")
        (field (name "DB_VOLTAGE") "6.3V")
        (field (name "DB_MANUFACTURER_PART") "KEMET    C0805C226M9PAC")
        (field (name "DB_APPROVED_BY") "ISHIDDEN=T")
      )
      (libsource (lib "Database_Libs1") (part "C"))
    )
    (comp (ref "C145")
      (value "22uF")
      (footprint "SMD_0805_CAPC2012X145N")
      (fields
        (field (name "DB_PART_NUMBER") "CAP000043686")
        (field (name "DB_VALUE") "22uF")
        (field (name "DB_TOLERANCE") "20%")
        (field (name "DB_VOLTAGE") "6.3V")
        (field (name "DB_MANUFACTURER_PART") "KEMET    C0805C226M9PAC")
        (field (name "DB_APPROVED_BY") "ISHIDDEN=T")
      )
      (libsource (lib "Database_Libs1") (part "C"))
    )
    (comp (ref "C146")
      (value "220uF")
      (footprint "SMD_1210_CAPC3225X279N")
      (fields
        (field (name "DB_PART_NUMBER") "CAP000047355")
        (field (name "DB_VALUE") "220uF")
        (field (name "DB_TOLERANCE") "20%")
        (field (name "DB_VOLTAGE") "6.3V")
        (field (name "DB_MANUFACTURER_PART") "SAMSUNG    CL32A227MQVNNNE")
        (field (name "DB_APPROVED_BY") "VSN")
      )
      (libsource (lib "Database_Libs1") (part "C"))
    )
    (comp (ref "C147")
      (value "22uF")
      (footprint "SMD_0805_CAPC2012X145N")
      (fields
        (field (name "DB_PART_NUMBER") "CAP000043686")
        (field (name "DB_VALUE") "22uF")
        (field (name "DB_TOLERANCE") "20%")
        (field (name "DB_VOLTAGE") "6.3V")
        (field (name "DB_MANUFACTURER_PART") "KEMET    C0805C226M9PAC")
        (field (name "DB_APPROVED_BY") "ISHIDDEN=T")
      )
      (libsource (lib "Database_Libs1") (part "C"))
    )
    (comp (ref "C166")
      (value "22uF")
      (footprint "SMD_0805_CAPC2012X145N")
      (fields
        (field (name "DB_PART_NUMBER") "CAP000043686")
        (field (name "DB_VALUE") "22uF")
        (field (name "DB_TOLERANCE") "20%")
        (field (name "DB_VOLTAGE") "6.3V")
        (field (name "DB_MANUFACTURER_PART") "KEMET    C0805C226M9PAC")
        (field (name "DB_APPROVED_BY") "ISHIDDEN=T")
      )
      (libsource (lib "Database_Libs1") (part "C"))
    )
    (comp (ref "C167")
      (value "220uF")
      (footprint "SMD_1210_CAPC3225X279N")
      (fields
        (field (name "DB_PART_NUMBER") "CAP000047355")
        (field (name "DB_VALUE") "220uF")
        (field (name "DB_TOLERANCE") "20%")
        (field (name "DB_VOLTAGE") "6.3V")
        (field (name "DB_MANUFACTURER_PART") "SAMSUNG    CL32A227MQVNNNE")
        (field (name "DB_APPROVED_BY") "VSN")
      )
      (libsource (lib "Database_Libs1") (part "C"))
    )
    (comp (ref "C169")
      (value "22uF")
      (footprint "SMD_0805_CAPC2012X145N")
      (fields
        (field (name "DB_PART_NUMBER") "CAP000043686")
        (field (name "DB_VALUE") "22uF")
        (field (name "DB_TOLERANCE") "20%")
        (field (name "DB_VOLTAGE") "6.3V")
        (field (name "DB_MANUFACTURER_PART") "KEMET    C0805C226M9PAC")
        (field (name "DB_APPROVED_BY") "ISHIDDEN=T")
      )
      (libsource (lib "Database_Libs1") (part "C"))
    )
    (comp (ref "C170")
      (value "22uF")
      (footprint "SMD_0805_CAPC2012X145N")
      (fields
        (field (name "DB_PART_NUMBER") "CAP000043686")
        (field (name "DB_VALUE") "22uF")
        (field (name "DB_TOLERANCE") "20%")
        (field (name "DB_VOLTAGE") "6.3V")
        (field (name "DB_MANUFACTURER_PART") "KEMET    C0805C226M9PAC")
        (field (name "DB_APPROVED_BY") "ISHIDDEN=T")
      )
      (libsource (lib "Database_Libs1") (part "C"))
    )
    (comp (ref "C172")
      (value "22uF")
      (footprint "SMD_0805_CAPC2012X145N")
      (fields
        (field (name "DB_PART_NUMBER") "CAP000043686")
        (field (name "DB_VALUE") "22uF")
        (field (name "DB_TOLERANCE") "20%")
        (field (name "DB_VOLTAGE") "6.3V")
        (field (name "DB_MANUFACTURER_PART") "KEMET    C0805C226M9PAC")
        (field (name "DB_APPROVED_BY") "ISHIDDEN=T")
      )
      (libsource (lib "Database_Libs1") (part "C"))
    )
    (comp (ref "C173")
      (value "22uF")
      (footprint "SMD_0805_CAPC2012X145N")
      (fields
        (field (name "DB_PART_NUMBER") "CAP000043686")
        (field (name "DB_VALUE") "22uF")
        (field (name "DB_TOLERANCE") "20%")
        (field (name "DB_VOLTAGE") "6.3V")
        (field (name "DB_MANUFACTURER_PART") "KEMET    C0805C226M9PAC")
        (field (name "DB_APPROVED_BY") "ISHIDDEN=T")
      )
      (libsource (lib "Database_Libs1") (part "C"))
    )
    (comp (ref "C174")
      (value "220uF")
      (footprint "SMD_1210_CAPC3225X279N")
      (fields
        (field (name "DB_PART_NUMBER") "CAP000047355")
        (field (name "DB_VALUE") "220uF")
        (field (name "DB_TOLERANCE") "20%")
        (field (name "DB_VOLTAGE") "6.3V")
        (field (name "DB_MANUFACTURER_PART") "SAMSUNG    CL32A227MQVNNNE")
        (field (name "DB_APPROVED_BY") "VSN")
      )
      (libsource (lib "Database_Libs1") (part "C"))
    )
    (comp (ref "C175")
      (value "22uF")
      (footprint "SMD_0805_CAPC2012X145N")
      (fields
        (field (name "DB_PART_NUMBER") "CAP000043686")
        (field (name "DB_VALUE") "22uF")
        (field (name "DB_TOLERANCE") "20%")
        (field (name "DB_VOLTAGE") "6.3V")
        (field (name "DB_MANUFACTURER_PART") "KEMET    C0805C226M9PAC")
        (field (name "DB_APPROVED_BY") "ISHIDDEN=T")
      )
      (libsource (lib "Database_Libs1") (part "C"))
    )
    (comp (ref "C176")
      (value "22uF")
      (footprint "SMD_0805_CAPC2012X145N")
      (fields
        (field (name "DB_PART_NUMBER") "CAP000043686")
        (field (name "DB_VALUE") "22uF")
        (field (name "DB_TOLERANCE") "20%")
        (field (name "DB_VOLTAGE") "6.3V")
        (field (name "DB_MANUFACTURER_PART") "KEMET    C0805C226M9PAC")
        (field (name "DB_APPROVED_BY") "ISHIDDEN=T")
      )
      (libsource (lib "Database_Libs1") (part "C"))
    )
    (comp (ref "C187")
      (value "22uF")
      (footprint "SMD_0805_CAPC2012X145N")
      (fields
        (field (name "DB_PART_NUMBER") "CAP000043686")
        (field (name "DB_VALUE") "22uF")
        (field (name "DB_TOLERANCE") "20%")
        (field (name "DB_VOLTAGE") "6.3V")
        (field (name "DB_MANUFACTURER_PART") "KEMET    C0805C226M9PAC")
        (field (name "DB_APPROVED_BY") "ISHIDDEN=T")
      )
      (libsource (lib "Database_Libs1") (part "C"))
    )
    (comp (ref "C188")
      (value "22uF")
      (footprint "SMD_0805_CAPC2012X145N")
      (fields
        (field (name "DB_PART_NUMBER") "CAP000043686")
        (field (name "DB_VALUE") "22uF")
        (field (name "DB_TOLERANCE") "20%")
        (field (name "DB_VOLTAGE") "6.3V")
        (field (name "DB_MANUFACTURER_PART") "KEMET    C0805C226M9PAC")
        (field (name "DB_APPROVED_BY") "ISHIDDEN=T")
      )
      (libsource (lib "Database_Libs1") (part "C"))
    )
    (comp (ref "C189")
      (value "220uF")
      (footprint "SMD_1210_CAPC3225X279N")
      (fields
        (field (name "DB_PART_NUMBER") "CAP000047355")
        (field (name "DB_VALUE") "220uF")
        (field (name "DB_TOLERANCE") "20%")
        (field (name "DB_VOLTAGE") "6.3V")
        (field (name "DB_MANUFACTURER_PART") "SAMSUNG    CL32A227MQVNNNE")
        (field (name "DB_APPROVED_BY") "VSN")
      )
      (libsource (lib "Database_Libs1") (part "C"))
    )
    (comp (ref "C190")
      (value "22uF")
      (footprint "SMD_0805_CAPC2012X145N")
      (fields
        (field (name "DB_PART_NUMBER") "CAP000043686")
        (field (name "DB_VALUE") "22uF")
        (field (name "DB_TOLERANCE") "20%")
        (field (name "DB_VOLTAGE") "6.3V")
        (field (name "DB_MANUFACTURER_PART") "KEMET    C0805C226M9PAC")
        (field (name "DB_APPROVED_BY") "ISHIDDEN=T")
      )
      (libsource (lib "Database_Libs1") (part "C"))
    )
    (comp (ref "C191")
      (value "22uF")
      (footprint "SMD_0805_CAPC2012X145N")
      (fields
        (field (name "DB_PART_NUMBER") "CAP000043686")
        (field (name "DB_VALUE") "22uF")
        (field (name "DB_TOLERANCE") "20%")
        (field (name "DB_VOLTAGE") "6.3V")
        (field (name "DB_MANUFACTURER_PART") "KEMET    C0805C226M9PAC")
        (field (name "DB_APPROVED_BY") "ISHIDDEN=T")
      )
      (libsource (lib "Database_Libs1") (part "C"))
    )
    (comp (ref "C192")
      (value "220uF")
      (footprint "SMD_1210_CAPC3225X279N")
      (fields
        (field (name "DB_PART_NUMBER") "CAP000047355")
        (field (name "DB_VALUE") "220uF")
        (field (name "DB_TOLERANCE") "20%")
        (field (name "DB_VOLTAGE") "6.3V")
        (field (name "DB_MANUFACTURER_PART") "SAMSUNG    CL32A227MQVNNNE")
        (field (name "DB_APPROVED_BY") "VSN")
      )
      (libsource (lib "Database_Libs1") (part "C"))
    )
    (comp (ref "C193")
      (value "22uF")
      (footprint "SMD_0805_CAPC2012X145N")
      (fields
        (field (name "DB_PART_NUMBER") "CAP000043686")
        (field (name "DB_VALUE") "22uF")
        (field (name "DB_TOLERANCE") "20%")
        (field (name "DB_VOLTAGE") "6.3V")
        (field (name "DB_MANUFACTURER_PART") "KEMET    C0805C226M9PAC")
        (field (name "DB_APPROVED_BY") "ISHIDDEN=T")
      )
      (libsource (lib "Database_Libs1") (part "C"))
    )
    (comp (ref "C194")
      (value "22uF")
      (footprint "SMD_0805_CAPC2012X145N")
      (fields
        (field (name "DB_PART_NUMBER") "CAP000043686")
        (field (name "DB_VALUE") "22uF")
        (field (name "DB_TOLERANCE") "20%")
        (field (name "DB_VOLTAGE") "6.3V")
        (field (name "DB_MANUFACTURER_PART") "KEMET    C0805C226M9PAC")
        (field (name "DB_APPROVED_BY") "ISHIDDEN=T")
      )
      (libsource (lib "Database_Libs1") (part "C"))
    )
    (comp (ref "C195")
      (value "220uF")
      (footprint "SMD_1210_CAPC3225X279N")
      (fields
        (field (name "DB_PART_NUMBER") "CAP000047355")
        (field (name "DB_VALUE") "220uF")
        (field (name "DB_TOLERANCE") "20%")
        (field (name "DB_VOLTAGE") "6.3V")
        (field (name "DB_MANUFACTURER_PART") "SAMSUNG    CL32A227MQVNNNE")
        (field (name "DB_APPROVED_BY") "VSN")
      )
      (libsource (lib "Database_Libs1") (part "C"))
    )
    (comp (ref "C196")
      (value "22uF")
      (footprint "SMD_0805_CAPC2012X145N")
      (fields
        (field (name "DB_PART_NUMBER") "CAP000043686")
        (field (name "DB_VALUE") "22uF")
        (field (name "DB_TOLERANCE") "20%")
        (field (name "DB_VOLTAGE") "6.3V")
        (field (name "DB_MANUFACTURER_PART") "KEMET    C0805C226M9PAC")
        (field (name "DB_APPROVED_BY") "ISHIDDEN=T")
      )
      (libsource (lib "Database_Libs1") (part "C"))
    )
    (comp (ref "C197")
      (value "22uF")
      (footprint "SMD_0805_CAPC2012X145N")
      (fields
        (field (name "DB_PART_NUMBER") "CAP000043686")
        (field (name "DB_VALUE") "22uF")
        (field (name "DB_TOLERANCE") "20%")
        (field (name "DB_VOLTAGE") "6.3V")
        (field (name "DB_MANUFACTURER_PART") "KEMET    C0805C226M9PAC")
        (field (name "DB_APPROVED_BY") "ISHIDDEN=T")
      )
      (libsource (lib "Database_Libs1") (part "C"))
    )
    (comp (ref "C199")
      (value "22uF")
      (footprint "SMD_0805_CAPC2012X145N")
      (fields
        (field (name "DB_PART_NUMBER") "CAP000043686")
        (field (name "DB_VALUE") "22uF")
        (field (name "DB_TOLERANCE") "20%")
        (field (name "DB_VOLTAGE") "6.3V")
        (field (name "DB_MANUFACTURER_PART") "KEMET    C0805C226M9PAC")
        (field (name "DB_APPROVED_BY") "ISHIDDEN=T")
      )
      (libsource (lib "Database_Libs1") (part "C"))
    )
    (comp (ref "C200")
      (value "22uF")
      (footprint "SMD_0805_CAPC2012X145N")
      (fields
        (field (name "DB_PART_NUMBER") "CAP000043686")
        (field (name "DB_VALUE") "22uF")
        (field (name "DB_TOLERANCE") "20%")
        (field (name "DB_VOLTAGE") "6.3V")
        (field (name "DB_MANUFACTURER_PART") "KEMET    C0805C226M9PAC")
        (field (name "DB_APPROVED_BY") "ISHIDDEN=T")
      )
      (libsource (lib "Database_Libs1") (part "C"))
    )
    (comp (ref "C202")
      (value "22uF")
      (footprint "SMD_0805_CAPC2012X145N")
      (fields
        (field (name "DB_PART_NUMBER") "CAP000043686")
        (field (name "DB_VALUE") "22uF")
        (field (name "DB_TOLERANCE") "20%")
        (field (name "DB_VOLTAGE") "6.3V")
        (field (name "DB_MANUFACTURER_PART") "KEMET    C0805C226M9PAC")
        (field (name "DB_APPROVED_BY") "ISHIDDEN=T")
      )
      (libsource (lib "Database_Libs1") (part "C"))
    )
    (comp (ref "C203")
      (value "22uF")
      (footprint "SMD_0805_CAPC2012X145N")
      (fields
        (field (name "DB_PART_NUMBER") "CAP000043686")
        (field (name "DB_VALUE") "22uF")
        (field (name "DB_TOLERANCE") "20%")
        (field (name "DB_VOLTAGE") "6.3V")
        (field (name "DB_MANUFACTURER_PART") "KEMET    C0805C226M9PAC")
        (field (name "DB_APPROVED_BY") "ISHIDDEN=T")
      )
      (libsource (lib "Database_Libs1") (part "C"))
    )
    (comp (ref "C205")
      (value "22uF")
      (footprint "SMD_0805_CAPC2012X145N")
      (fields
        (field (name "DB_PART_NUMBER") "CAP000043686")
        (field (name "DB_VALUE") "22uF")
        (field (name "DB_TOLERANCE") "20%")
        (field (name "DB_VOLTAGE") "6.3V")
        (field (name "DB_MANUFACTURER_PART") "KEMET    C0805C226M9PAC")
        (field (name "DB_APPROVED_BY") "ISHIDDEN=T")
      )
      (libsource (lib "Database_Libs1") (part "C"))
    )
    (comp (ref "C257")
      (value "220nF")
      (footprint "SMD_0603_CAPC1608X95N")
      (fields
        (field (name "DB_PART_NUMBER") "CAP000022968")
        (field (name "DB_VALUE") "220nF")
        (field (name "DB_TOLERANCE") "10%")
        (field (name "DB_VOLTAGE") "25V")
        (field (name "DB_MANUFACTURER_PART") "KEMET    C0603F224K3RAC")
        (field (name "DB_APPROVED_BY") "ISHIDDEN=T")
      )
      (libsource (lib "Database_Libs1") (part "C"))
    )
    (comp (ref "C258")
      (value "100uF")
      (footprint "SMD_1210_CAPC3225X270N")
      (fields
        (field (name "DB_PART_NUMBER") "TMP-2512")
        (field (name "DB_VALUE") "100uF")
        (field (name "DB_TOLERANCE") "20%")
        (field (name "DB_VOLTAGE") "16V")
        (field (name "DB_MANUFACTURER_PART") "YAGEO    CC1210MRX5R7BB107")
      )
      (libsource (lib "Database_Libs1") (part "C"))
    )
    (comp (ref "C259")
      (value "100uF")
      (footprint "SMD_1210_CAPC3225X270N")
      (fields
        (field (name "DB_PART_NUMBER") "TMP-2512")
        (field (name "DB_VALUE") "100uF")
        (field (name "DB_TOLERANCE") "20%")
        (field (name "DB_VOLTAGE") "16V")
        (field (name "DB_MANUFACTURER_PART") "YAGEO    CC1210MRX5R7BB107")
      )
      (libsource (lib "Database_Libs1") (part "C"))
    )
    (comp (ref "C260")
      (value "220uF")
      (footprint "SMD_1210_CAPC3225X279N")
      (fields
        (field (name "DB_PART_NUMBER") "CAP000047355")
        (field (name "DB_VALUE") "220uF")
        (field (name "DB_TOLERANCE") "20%")
        (field (name "DB_VOLTAGE") "6.3V")
        (field (name "DB_MANUFACTURER_PART") "SAMSUNG    CL32A227MQVNNNE")
        (field (name "DB_APPROVED_BY") "VSN")
      )
      (libsource (lib "Database_Libs1") (part "C"))
    )
    (comp (ref "C261")
      (value "220uF")
      (footprint "SMD_1210_CAPC3225X279N")
      (fields
        (field (name "DB_PART_NUMBER") "CAP000047355")
        (field (name "DB_VALUE") "220uF")
        (field (name "DB_TOLERANCE") "20%")
        (field (name "DB_VOLTAGE") "6.3V")
        (field (name "DB_MANUFACTURER_PART") "SAMSUNG    CL32A227MQVNNNE")
        (field (name "DB_APPROVED_BY") "VSN")
      )
      (libsource (lib "Database_Libs1") (part "C"))
    )
    (comp (ref "C262")
      (value "220uF")
      (footprint "SMD_1210_CAPC3225X279N")
      (fields
        (field (name "DB_PART_NUMBER") "CAP000047355")
        (field (name "DB_VALUE") "220uF")
        (field (name "DB_TOLERANCE") "20%")
        (field (name "DB_VOLTAGE") "6.3V")
        (field (name "DB_MANUFACTURER_PART") "SAMSUNG    CL32A227MQVNNNE")
        (field (name "DB_APPROVED_BY") "VSN")
      )
      (libsource (lib "Database_Libs1") (part "C"))
    )
    (comp (ref "C263")
      (value "22uF")
      (footprint "SMD_0805_CAPC2012X145N")
      (fields
        (field (name "DB_PART_NUMBER") "CAP000043686")
        (field (name "DB_VALUE") "22uF")
        (field (name "DB_TOLERANCE") "20%")
        (field (name "DB_VOLTAGE") "6.3V")
        (field (name "DB_MANUFACTURER_PART") "KEMET    C0805C226M9PAC")
        (field (name "DB_APPROVED_BY") "ISHIDDEN=T")
      )
      (libsource (lib "Database_Libs1") (part "C"))
    )
    (comp (ref "C264")
      (value "22uF")
      (footprint "SMD_0805_CAPC2012X145N")
      (fields
        (field (name "DB_PART_NUMBER") "CAP000043686")
        (field (name "DB_VALUE") "22uF")
        (field (name "DB_TOLERANCE") "20%")
        (field (name "DB_VOLTAGE") "6.3V")
        (field (name "DB_MANUFACTURER_PART") "KEMET    C0805C226M9PAC")
        (field (name "DB_APPROVED_BY") "ISHIDDEN=T")
      )
      (libsource (lib "Database_Libs1") (part "C"))
    )
    (comp (ref "C265")
      (value "22uF")
      (footprint "SMD_0805_CAPC2012X145N")
      (fields
        (field (name "DB_PART_NUMBER") "CAP000043686")
        (field (name "DB_VALUE") "22uF")
        (field (name "DB_TOLERANCE") "20%")
        (field (name "DB_VOLTAGE") "6.3V")
        (field (name "DB_MANUFACTURER_PART") "KEMET    C0805C226M9PAC")
        (field (name "DB_APPROVED_BY") "ISHIDDEN=T")
      )
      (libsource (lib "Database_Libs1") (part "C"))
    )
    (comp (ref "C266")
      (value "22uF")
      (footprint "SMD_0805_CAPC2012X145N")
      (fields
        (field (name "DB_PART_NUMBER") "CAP000043686")
        (field (name "DB_VALUE") "22uF")
        (field (name "DB_TOLERANCE") "20%")
        (field (name "DB_VOLTAGE") "6.3V")
        (field (name "DB_MANUFACTURER_PART") "KEMET    C0805C226M9PAC")
        (field (name "DB_APPROVED_BY") "ISHIDDEN=T")
      )
      (libsource (lib "Database_Libs1") (part "C"))
    )
    (comp (ref "C267")
      (value "220uF")
      (footprint "SMD_1210_CAPC3225X279N")
      (fields
        (field (name "DB_PART_NUMBER") "CAP000047355")
        (field (name "DB_VALUE") "220uF")
        (field (name "DB_TOLERANCE") "20%")
        (field (name "DB_VOLTAGE") "6.3V")
        (field (name "DB_MANUFACTURER_PART") "SAMSUNG    CL32A227MQVNNNE")
        (field (name "DB_APPROVED_BY") "VSN")
      )
      (libsource (lib "Database_Libs1") (part "C"))
    )
    (comp (ref "C268")
      (value "22uF")
      (footprint "SMD_0805_CAPC2012X145N")
      (fields
        (field (name "DB_PART_NUMBER") "CAP000043686")
        (field (name "DB_VALUE") "22uF")
        (field (name "DB_TOLERANCE") "20%")
        (field (name "DB_VOLTAGE") "6.3V")
        (field (name "DB_MANUFACTURER_PART") "KEMET    C0805C226M9PAC")
        (field (name "DB_APPROVED_BY") "ISHIDDEN=T")
      )
      (libsource (lib "Database_Libs1") (part "C"))
    )
    (comp (ref "C269")
      (value "22uF")
      (footprint "SMD_0805_CAPC2012X145N")
      (fields
        (field (name "DB_PART_NUMBER") "CAP000043686")
        (field (name "DB_VALUE") "22uF")
        (field (name "DB_TOLERANCE") "20%")
        (field (name "DB_VOLTAGE") "6.3V")
        (field (name "DB_MANUFACTURER_PART") "KEMET    C0805C226M9PAC")
        (field (name "DB_APPROVED_BY") "ISHIDDEN=T")
      )
      (libsource (lib "Database_Libs1") (part "C"))
    )
    (comp (ref "C270")
      (value "220uF")
      (footprint "SMD_1210_CAPC3225X279N")
      (fields
        (field (name "DB_PART_NUMBER") "CAP000047355")
        (field (name "DB_VALUE") "220uF")
        (field (name "DB_TOLERANCE") "20%")
        (field (name "DB_VOLTAGE") "6.3V")
        (field (name "DB_MANUFACTURER_PART") "SAMSUNG    CL32A227MQVNNNE")
        (field (name "DB_APPROVED_BY") "VSN")
      )
      (libsource (lib "Database_Libs1") (part "C"))
    )
    (comp (ref "C271")
      (value "22uF")
      (footprint "SMD_0805_CAPC2012X145N")
      (fields
        (field (name "DB_PART_NUMBER") "CAP000043686")
        (field (name "DB_VALUE") "22uF")
        (field (name "DB_TOLERANCE") "20%")
        (field (name "DB_VOLTAGE") "6.3V")
        (field (name "DB_MANUFACTURER_PART") "KEMET    C0805C226M9PAC")
        (field (name "DB_APPROVED_BY") "ISHIDDEN=T")
      )
      (libsource (lib "Database_Libs1") (part "C"))
    )
    (comp (ref "C272")
      (value "22uF")
      (footprint "SMD_0805_CAPC2012X145N")
      (fields
        (field (name "DB_PART_NUMBER") "CAP000043686")
        (field (name "DB_VALUE") "22uF")
        (field (name "DB_TOLERANCE") "20%")
        (field (name "DB_VOLTAGE") "6.3V")
        (field (name "DB_MANUFACTURER_PART") "KEMET    C0805C226M9PAC")
        (field (name "DB_APPROVED_BY") "ISHIDDEN=T")
      )
      (libsource (lib "Database_Libs1") (part "C"))
    )
    (comp (ref "C273")
      (value "220uF")
      (footprint "SMD_1210_CAPC3225X279N")
      (fields
        (field (name "DB_PART_NUMBER") "CAP000047355")
        (field (name "DB_VALUE") "220uF")
        (field (name "DB_TOLERANCE") "20%")
        (field (name "DB_VOLTAGE") "6.3V")
        (field (name "DB_MANUFACTURER_PART") "SAMSUNG    CL32A227MQVNNNE")
        (field (name "DB_APPROVED_BY") "VSN")
      )
      (libsource (lib "Database_Libs1") (part "C"))
    )
    (comp (ref "C274")
      (value "22uF")
      (footprint "SMD_0805_CAPC2012X145N")
      (fields
        (field (name "DB_PART_NUMBER") "CAP000043686")
        (field (name "DB_VALUE") "22uF")
        (field (name "DB_TOLERANCE") "20%")
        (field (name "DB_VOLTAGE") "6.3V")
        (field (name "DB_MANUFACTURER_PART") "KEMET    C0805C226M9PAC")
        (field (name "DB_APPROVED_BY") "ISHIDDEN=T")
      )
      (libsource (lib "Database_Libs1") (part "C"))
    )
    (comp (ref "C275")
      (value "22uF")
      (footprint "SMD_0805_CAPC2012X145N")
      (fields
        (field (name "DB_PART_NUMBER") "CAP000043686")
        (field (name "DB_VALUE") "22uF")
        (field (name "DB_TOLERANCE") "20%")
        (field (name "DB_VOLTAGE") "6.3V")
        (field (name "DB_MANUFACTURER_PART") "KEMET    C0805C226M9PAC")
        (field (name "DB_APPROVED_BY") "ISHIDDEN=T")
      )
      (libsource (lib "Database_Libs1") (part "C"))
    )
    (comp (ref "C276")
      (value "220uF")
      (footprint "SMD_1210_CAPC3225X279N")
      (fields
        (field (name "DB_PART_NUMBER") "CAP000047355")
        (field (name "DB_VALUE") "220uF")
        (field (name "DB_TOLERANCE") "20%")
        (field (name "DB_VOLTAGE") "6.3V")
        (field (name "DB_MANUFACTURER_PART") "SAMSUNG    CL32A227MQVNNNE")
        (field (name "DB_APPROVED_BY") "VSN")
      )
      (libsource (lib "Database_Libs1") (part "C"))
    )
    (comp (ref "C331")
      (value "22uF")
      (footprint "SMD_0805_CAPC2012X145N")
      (fields
        (field (name "DB_PART_NUMBER") "CAP000043686")
        (field (name "DB_VALUE") "22uF")
        (field (name "DB_TOLERANCE") "20%")
        (field (name "DB_VOLTAGE") "6.3V")
        (field (name "DB_MANUFACTURER_PART") "KEMET    C0805C226M9PAC")
        (field (name "DB_APPROVED_BY") "ISHIDDEN=T")
      )
      (libsource (lib "Database_Libs1") (part "C"))
    )
    (comp (ref "C332")
      (value "22uF")
      (footprint "SMD_0805_CAPC2012X145N")
      (fields
        (field (name "DB_PART_NUMBER") "CAP000043686")
        (field (name "DB_VALUE") "22uF")
        (field (name "DB_TOLERANCE") "20%")
        (field (name "DB_VOLTAGE") "6.3V")
        (field (name "DB_MANUFACTURER_PART") "KEMET    C0805C226M9PAC")
        (field (name "DB_APPROVED_BY") "ISHIDDEN=T")
      )
      (libsource (lib "Database_Libs1") (part "C"))
    )
    (comp (ref "C333")
      (value "22uF")
      (footprint "SMD_0805_CAPC2012X145N")
      (fields
        (field (name "DB_PART_NUMBER") "CAP000043686")
        (field (name "DB_VALUE") "22uF")
        (field (name "DB_TOLERANCE") "20%")
        (field (name "DB_VOLTAGE") "6.3V")
        (field (name "DB_MANUFACTURER_PART") "KEMET    C0805C226M9PAC")
        (field (name "DB_APPROVED_BY") "ISHIDDEN=T")
      )
      (libsource (lib "Database_Libs1") (part "C"))
    )
    (comp (ref "C334")
      (value "22uF")
      (footprint "SMD_0805_CAPC2012X145N")
      (fields
        (field (name "DB_PART_NUMBER") "CAP000043686")
        (field (name "DB_VALUE") "22uF")
        (field (name "DB_TOLERANCE") "20%")
        (field (name "DB_VOLTAGE") "6.3V")
        (field (name "DB_MANUFACTURER_PART") "KEMET    C0805C226M9PAC")
        (field (name "DB_APPROVED_BY") "ISHIDDEN=T")
      )
      (libsource (lib "Database_Libs1") (part "C"))
    )
    (comp (ref "C373")
      (value "100uF")
      (footprint "SMD_1210_CAPC3225X270N")
      (fields
        (field (name "DB_PART_NUMBER") "TMP-2512")
        (field (name "DB_VALUE") "100uF")
        (field (name "DB_TOLERANCE") "20%")
        (field (name "DB_VOLTAGE") "16V")
        (field (name "DB_MANUFACTURER_PART") "YAGEO    CC1210MRX5R7BB107")
      )
      (libsource (lib "Database_Libs1") (part "C"))
    )
    (comp (ref "C374")
      (value "100uF")
      (footprint "SMD_1210_CAPC3225X270N")
      (fields
        (field (name "DB_PART_NUMBER") "TMP-2512")
        (field (name "DB_VALUE") "100uF")
        (field (name "DB_TOLERANCE") "20%")
        (field (name "DB_VOLTAGE") "16V")
        (field (name "DB_MANUFACTURER_PART") "YAGEO    CC1210MRX5R7BB107")
      )
      (libsource (lib "Database_Libs1") (part "C"))
    )
    (comp (ref "C375")
      (value "220uF")
      (footprint "SMD_1210_CAPC3225X279N")
      (fields
        (field (name "DB_PART_NUMBER") "CAP000047355")
        (field (name "DB_VALUE") "220uF")
        (field (name "DB_TOLERANCE") "20%")
        (field (name "DB_VOLTAGE") "6.3V")
        (field (name "DB_MANUFACTURER_PART") "SAMSUNG    CL32A227MQVNNNE")
        (field (name "DB_APPROVED_BY") "VSN")
      )
      (libsource (lib "Database_Libs1") (part "C"))
    )
    (comp (ref "C376")
      (value "220uF")
      (footprint "SMD_1210_CAPC3225X279N")
      (fields
        (field (name "DB_PART_NUMBER") "CAP000047355")
        (field (name "DB_VALUE") "220uF")
        (field (name "DB_TOLERANCE") "20%")
        (field (name "DB_VOLTAGE") "6.3V")
        (field (name "DB_MANUFACTURER_PART") "SAMSUNG    CL32A227MQVNNNE")
        (field (name "DB_APPROVED_BY") "VSN")
      )
      (libsource (lib "Database_Libs1") (part "C"))
    )
    (comp (ref "C377")
      (value "220uF")
      (footprint "SMD_1210_CAPC3225X279N")
      (fields
        (field (name "DB_PART_NUMBER") "CAP000047355")
        (field (name "DB_VALUE") "220uF")
        (field (name "DB_TOLERANCE") "20%")
        (field (name "DB_VOLTAGE") "6.3V")
        (field (name "DB_MANUFACTURER_PART") "SAMSUNG    CL32A227MQVNNNE")
        (field (name "DB_APPROVED_BY") "VSN")
      )
      (libsource (lib "Database_Libs1") (part "C"))
    )
    (comp (ref "C378")
      (value "10uF")
      (footprint "SMD_0805_CAPC2012X145N")
      (fields
        (field (name "DB_PART_NUMBER") "CAP000043636")
        (field (name "DB_VALUE") "10uF")
        (field (name "DB_TOLERANCE") "10%")
        (field (name "DB_VOLTAGE") "16V")
        (field (name "DB_MANUFACTURER_PART") "KEMET    C0805C106K4PAC")
        (field (name "DB_APPROVED_BY") "ISHIDDEN=T")
      )
      (libsource (lib "Database_Libs1") (part "C"))
    )
    (comp (ref "C379")
      (value "10uF")
      (footprint "SMD_0805_CAPC2012X145N")
      (fields
        (field (name "DB_PART_NUMBER") "CAP000043636")
        (field (name "DB_VALUE") "10uF")
        (field (name "DB_TOLERANCE") "10%")
        (field (name "DB_VOLTAGE") "16V")
        (field (name "DB_MANUFACTURER_PART") "KEMET    C0805C106K4PAC")
        (field (name "DB_APPROVED_BY") "ISHIDDEN=T")
      )
      (libsource (lib "Database_Libs1") (part "C"))
    )
    (comp (ref "C380")
      (value "10uF")
      (footprint "SMD_0805_CAPC2012X145N")
      (fields
        (field (name "DB_PART_NUMBER") "CAP000043636")
        (field (name "DB_VALUE") "10uF")
        (field (name "DB_TOLERANCE") "10%")
        (field (name "DB_VOLTAGE") "16V")
        (field (name "DB_MANUFACTURER_PART") "KEMET    C0805C106K4PAC")
        (field (name "DB_APPROVED_BY") "ISHIDDEN=T")
      )
      (libsource (lib "Database_Libs1") (part "C"))
    )
    (comp (ref "C381")
      (value "220uF")
      (footprint "SMD_1210_CAPC3225X279N")
      (fields
        (field (name "DB_PART_NUMBER") "CAP000047355")
        (field (name "DB_VALUE") "220uF")
        (field (name "DB_TOLERANCE") "20%")
        (field (name "DB_VOLTAGE") "6.3V")
        (field (name "DB_MANUFACTURER_PART") "SAMSUNG    CL32A227MQVNNNE")
        (field (name "DB_APPROVED_BY") "VSN")
      )
      (libsource (lib "Database_Libs1") (part "C"))
    )
    (comp (ref "C382")
      (value "220uF")
      (footprint "SMD_1210_CAPC3225X279N")
      (fields
        (field (name "DB_PART_NUMBER") "CAP000047355")
        (field (name "DB_VALUE") "220uF")
        (field (name "DB_TOLERANCE") "20%")
        (field (name "DB_VOLTAGE") "6.3V")
        (field (name "DB_MANUFACTURER_PART") "SAMSUNG    CL32A227MQVNNNE")
        (field (name "DB_APPROVED_BY") "VSN")
      )
      (libsource (lib "Database_Libs1") (part "C"))
    )
    (comp (ref "C397")
      (value "220uF")
      (footprint "SMD_1210_CAPC3225X279N")
      (fields
        (field (name "DB_PART_NUMBER") "CAP000047355")
        (field (name "DB_VALUE") "220uF")
        (field (name "DB_TOLERANCE") "20%")
        (field (name "DB_VOLTAGE") "6.3V")
        (field (name "DB_MANUFACTURER_PART") "SAMSUNG    CL32A227MQVNNNE")
        (field (name "DB_APPROVED_BY") "VSN")
      )
      (libsource (lib "Database_Libs1") (part "C"))
    )
    (comp (ref "C398")
      (value "220uF")
      (footprint "SMD_1210_CAPC3225X279N")
      (fields
        (field (name "DB_PART_NUMBER") "CAP000047355")
        (field (name "DB_VALUE") "220uF")
        (field (name "DB_TOLERANCE") "20%")
        (field (name "DB_VOLTAGE") "6.3V")
        (field (name "DB_MANUFACTURER_PART") "SAMSUNG    CL32A227MQVNNNE")
        (field (name "DB_APPROVED_BY") "VSN")
      )
      (libsource (lib "Database_Libs1") (part "C"))
    )
    (comp (ref "C399")
      (value "220uF")
      (footprint "SMD_1210_CAPC3225X279N")
      (fields
        (field (name "DB_PART_NUMBER") "CAP000047355")
        (field (name "DB_VALUE") "220uF")
        (field (name "DB_TOLERANCE") "20%")
        (field (name "DB_VOLTAGE") "6.3V")
        (field (name "DB_MANUFACTURER_PART") "SAMSUNG    CL32A227MQVNNNE")
        (field (name "DB_APPROVED_BY") "VSN")
      )
      (libsource (lib "Database_Libs1") (part "C"))
    )
    (comp (ref "C400")
      (value "220uF")
      (footprint "SMD_1210_CAPC3225X279N")
      (fields
        (field (name "DB_PART_NUMBER") "CAP000047355")
        (field (name "DB_VALUE") "220uF")
        (field (name "DB_TOLERANCE") "20%")
        (field (name "DB_VOLTAGE") "6.3V")
        (field (name "DB_MANUFACTURER_PART") "SAMSUNG    CL32A227MQVNNNE")
        (field (name "DB_APPROVED_BY") "VSN")
      )
      (libsource (lib "Database_Libs1") (part "C"))
    )
    (comp (ref "C401")
      (value "220uF")
      (footprint "SMD_1210_CAPC3225X279N")
      (fields
        (field (name "DB_PART_NUMBER") "CAP000047355")
        (field (name "DB_VALUE") "220uF")
        (field (name "DB_TOLERANCE") "20%")
        (field (name "DB_VOLTAGE") "6.3V")
        (field (name "DB_MANUFACTURER_PART") "SAMSUNG    CL32A227MQVNNNE")
        (field (name "DB_APPROVED_BY") "VSN")
      )
      (libsource (lib "Database_Libs1") (part "C"))
    )
    (comp (ref "C404")
      (value "100uF")
      (footprint "SMD_1210_CAPC3225X270N")
      (fields
        (field (name "DB_PART_NUMBER") "TMP-2512")
        (field (name "DB_VALUE") "100uF")
        (field (name "DB_TOLERANCE") "20%")
        (field (name "DB_VOLTAGE") "16V")
        (field (name "DB_MANUFACTURER_PART") "YAGEO    CC1210MRX5R7BB107")
      )
      (libsource (lib "Database_Libs1") (part "C"))
    )
    (comp (ref "C405")
      (value "100uF")
      (footprint "SMD_1210_CAPC3225X270N")
      (fields
        (field (name "DB_PART_NUMBER") "TMP-2512")
        (field (name "DB_VALUE") "100uF")
        (field (name "DB_TOLERANCE") "20%")
        (field (name "DB_VOLTAGE") "16V")
        (field (name "DB_MANUFACTURER_PART") "YAGEO    CC1210MRX5R7BB107")
      )
      (libsource (lib "Database_Libs1") (part "C"))
    )
    (comp (ref "C406")
      (value "100uF")
      (footprint "SMD_1210_CAPC3225X270N")
      (fields
        (field (name "DB_PART_NUMBER") "TMP-2512")
        (field (name "DB_VALUE") "100uF")
        (field (name "DB_TOLERANCE") "20%")
        (field (name "DB_VOLTAGE") "16V")
        (field (name "DB_MANUFACTURER_PART") "YAGEO    CC1210MRX5R7BB107")
      )
      (libsource (lib "Database_Libs1") (part "C"))
    )
    (comp (ref "C407")
      (value "100uF")
      (footprint "SMD_1210_CAPC3225X270N")
      (fields
        (field (name "DB_PART_NUMBER") "TMP-2512")
        (field (name "DB_VALUE") "100uF")
        (field (name "DB_TOLERANCE") "20%")
        (field (name "DB_VOLTAGE") "16V")
        (field (name "DB_MANUFACTURER_PART") "YAGEO    CC1210MRX5R7BB107")
      )
      (libsource (lib "Database_Libs1") (part "C"))
    )
    (comp (ref "C596")
      (value "100uF")
      (footprint "SMD_1210_CAPC3225X270N")
      (fields
        (field (name "DB_PART_NUMBER") "TMP-2512")
        (field (name "DB_VALUE") "100uF")
        (field (name "DB_TOLERANCE") "20%")
        (field (name "DB_VOLTAGE") "16V")
        (field (name "DB_MANUFACTURER_PART") "YAGEO    CC1210MRX5R7BB107")
      )
      (libsource (lib "Database_Libs1") (part "C"))
    )
    (comp (ref "C598")
      (value "10uF")
      (footprint "SMD_0805_CAPC2012X145N")
      (fields
        (field (name "DB_PART_NUMBER") "CAP000043636")
        (field (name "DB_VALUE") "10uF")
        (field (name "DB_TOLERANCE") "10%")
        (field (name "DB_VOLTAGE") "16V")
        (field (name "DB_MANUFACTURER_PART") "KEMET    C0805C106K4PAC")
        (field (name "DB_APPROVED_BY") "ISHIDDEN=T")
      )
      (libsource (lib "Database_Libs1") (part "C"))
    )
    (comp (ref "C599")
      (value "100uF")
      (footprint "SMD_1210_CAPC3225X270N")
      (fields
        (field (name "DB_PART_NUMBER") "TMP-2512")
        (field (name "DB_VALUE") "100uF")
        (field (name "DB_TOLERANCE") "20%")
        (field (name "DB_VOLTAGE") "16V")
        (field (name "DB_MANUFACTURER_PART") "YAGEO    CC1210MRX5R7BB107")
      )
      (libsource (lib "Database_Libs1") (part "C"))
    )
    (comp (ref "C600")
      (value "10uF")
      (footprint "SMD_0805_CAPC2012X145N")
      (fields
        (field (name "DB_PART_NUMBER") "CAP000043636")
        (field (name "DB_VALUE") "10uF")
        (field (name "DB_TOLERANCE") "10%")
        (field (name "DB_VOLTAGE") "16V")
        (field (name "DB_MANUFACTURER_PART") "KEMET    C0805C106K4PAC")
        (field (name "DB_APPROVED_BY") "ISHIDDEN=T")
      )
      (libsource (lib "Database_Libs1") (part "C"))
    )
    (comp (ref "C602")
      (value "100uF")
      (footprint "SMD_1210_CAPC3225X270N")
      (fields
        (field (name "DB_PART_NUMBER") "TMP-2512")
        (field (name "DB_VALUE") "100uF")
        (field (name "DB_TOLERANCE") "20%")
        (field (name "DB_VOLTAGE") "16V")
        (field (name "DB_MANUFACTURER_PART") "YAGEO    CC1210MRX5R7BB107")
      )
      (libsource (lib "Database_Libs1") (part "C"))
    )
    (comp (ref "C603")
      (value "10uF")
      (footprint "SMD_0805_CAPC2012X145N")
      (fields
        (field (name "DB_PART_NUMBER") "CAP000043636")
        (field (name "DB_VALUE") "10uF")
        (field (name "DB_TOLERANCE") "10%")
        (field (name "DB_VOLTAGE") "16V")
        (field (name "DB_MANUFACTURER_PART") "KEMET    C0805C106K4PAC")
        (field (name "DB_APPROVED_BY") "ISHIDDEN=T")
      )
      (libsource (lib "Database_Libs1") (part "C"))
    )
    (comp (ref "C605")
      (value "100uF")
      (footprint "SMD_1210_CAPC3225X270N")
      (fields
        (field (name "DB_PART_NUMBER") "TMP-2512")
        (field (name "DB_VALUE") "100uF")
        (field (name "DB_TOLERANCE") "20%")
        (field (name "DB_VOLTAGE") "16V")
        (field (name "DB_MANUFACTURER_PART") "YAGEO    CC1210MRX5R7BB107")
      )
      (libsource (lib "Database_Libs1") (part "C"))
    )
    (comp (ref "C606")
      (value "10uF")
      (footprint "SMD_0805_CAPC2012X145N")
      (fields
        (field (name "DB_PART_NUMBER") "CAP000043636")
        (field (name "DB_VALUE") "10uF")
        (field (name "DB_TOLERANCE") "10%")
        (field (name "DB_VOLTAGE") "16V")
        (field (name "DB_MANUFACTURER_PART") "KEMET    C0805C106K4PAC")
        (field (name "DB_APPROVED_BY") "ISHIDDEN=T")
      )
      (libsource (lib "Database_Libs1") (part "C"))
    )
    (comp (ref "C640")
      (value "10uF")
      (footprint "SMD_0805_CAPC2012X145N")
      (fields
        (field (name "DB_PART_NUMBER") "CAP000043636")
        (field (name "DB_VALUE") "10uF")
        (field (name "DB_TOLERANCE") "10%")
        (field (name "DB_VOLTAGE") "16V")
        (field (name "DB_MANUFACTURER_PART") "KEMET    C0805C106K4PAC")
        (field (name "DB_APPROVED_BY") "ISHIDDEN=T")
      )
      (libsource (lib "Database_Libs1") (part "C"))
    )
    (comp (ref "C642")
      (value "10uF")
      (footprint "SMD_0805_CAPC2012X145N")
      (fields
        (field (name "DB_PART_NUMBER") "CAP000043636")
        (field (name "DB_VALUE") "10uF")
        (field (name "DB_TOLERANCE") "10%")
        (field (name "DB_VOLTAGE") "16V")
        (field (name "DB_MANUFACTURER_PART") "KEMET    C0805C106K4PAC")
        (field (name "DB_APPROVED_BY") "ISHIDDEN=T")
      )
      (libsource (lib "Database_Libs1") (part "C"))
    )
    (comp (ref "C652")
      (value "22uF")
      (footprint "SMD_0805_CAPC2012X145N")
      (fields
        (field (name "DB_PART_NUMBER") "CAP000043686")
        (field (name "DB_VALUE") "22uF")
        (field (name "DB_TOLERANCE") "20%")
        (field (name "DB_VOLTAGE") "6.3V")
        (field (name "DB_MANUFACTURER_PART") "KEMET    C0805C226M9PAC")
        (field (name "DB_APPROVED_BY") "ISHIDDEN=T")
      )
      (libsource (lib "Database_Libs1") (part "C"))
    )
    (comp (ref "C653")
      (value "220uF")
      (footprint "SMD_1210_CAPC3225X279N")
      (fields
        (field (name "DB_PART_NUMBER") "CAP000047355")
        (field (name "DB_VALUE") "220uF")
        (field (name "DB_TOLERANCE") "20%")
        (field (name "DB_VOLTAGE") "6.3V")
        (field (name "DB_MANUFACTURER_PART") "SAMSUNG    CL32A227MQVNNNE")
        (field (name "DB_APPROVED_BY") "VSN")
      )
      (libsource (lib "Database_Libs1") (part "C"))
    )
    (comp (ref "C654")
      (value "22uF")
      (footprint "SMD_0805_CAPC2012X145N")
      (fields
        (field (name "DB_PART_NUMBER") "CAP000043686")
        (field (name "DB_VALUE") "22uF")
        (field (name "DB_TOLERANCE") "20%")
        (field (name "DB_VOLTAGE") "6.3V")
        (field (name "DB_MANUFACTURER_PART") "KEMET    C0805C226M9PAC")
        (field (name "DB_APPROVED_BY") "ISHIDDEN=T")
      )
      (libsource (lib "Database_Libs1") (part "C"))
    )
    (comp (ref "C655")
      (value "22uF")
      (footprint "SMD_0805_CAPC2012X145N")
      (fields
        (field (name "DB_PART_NUMBER") "CAP000043686")
        (field (name "DB_VALUE") "22uF")
        (field (name "DB_TOLERANCE") "20%")
        (field (name "DB_VOLTAGE") "6.3V")
        (field (name "DB_MANUFACTURER_PART") "KEMET    C0805C226M9PAC")
        (field (name "DB_APPROVED_BY") "ISHIDDEN=T")
      )
      (libsource (lib "Database_Libs1") (part "C"))
    )
    (comp (ref "C656")
      (value "220uF")
      (footprint "SMD_1210_CAPC3225X279N")
      (fields
        (field (name "DB_PART_NUMBER") "CAP000047355")
        (field (name "DB_VALUE") "220uF")
        (field (name "DB_TOLERANCE") "20%")
        (field (name "DB_VOLTAGE") "6.3V")
        (field (name "DB_MANUFACTURER_PART") "SAMSUNG    CL32A227MQVNNNE")
        (field (name "DB_APPROVED_BY") "VSN")
      )
      (libsource (lib "Database_Libs1") (part "C"))
    )
    (comp (ref "C657")
      (value "22uF")
      (footprint "SMD_0805_CAPC2012X145N")
      (fields
        (field (name "DB_PART_NUMBER") "CAP000043686")
        (field (name "DB_VALUE") "22uF")
        (field (name "DB_TOLERANCE") "20%")
        (field (name "DB_VOLTAGE") "6.3V")
        (field (name "DB_MANUFACTURER_PART") "KEMET    C0805C226M9PAC")
        (field (name "DB_APPROVED_BY") "ISHIDDEN=T")
      )
      (libsource (lib "Database_Libs1") (part "C"))
    )
    (comp (ref "C658")
      (value "22uF")
      (footprint "SMD_0805_CAPC2012X145N")
      (fields
        (field (name "DB_PART_NUMBER") "CAP000043686")
        (field (name "DB_VALUE") "22uF")
        (field (name "DB_TOLERANCE") "20%")
        (field (name "DB_VOLTAGE") "6.3V")
        (field (name "DB_MANUFACTURER_PART") "KEMET    C0805C226M9PAC")
        (field (name "DB_APPROVED_BY") "ISHIDDEN=T")
      )
      (libsource (lib "Database_Libs1") (part "C"))
    )
    (comp (ref "C659")
      (value "220uF")
      (footprint "SMD_1210_CAPC3225X279N")
      (fields
        (field (name "DB_PART_NUMBER") "CAP000047355")
        (field (name "DB_VALUE") "220uF")
        (field (name "DB_TOLERANCE") "20%")
        (field (name "DB_VOLTAGE") "6.3V")
        (field (name "DB_MANUFACTURER_PART") "SAMSUNG    CL32A227MQVNNNE")
        (field (name "DB_APPROVED_BY") "VSN")
      )
      (libsource (lib "Database_Libs1") (part "C"))
    )
    (comp (ref "C660")
      (value "22uF")
      (footprint "SMD_0805_CAPC2012X145N")
      (fields
        (field (name "DB_PART_NUMBER") "CAP000043686")
        (field (name "DB_VALUE") "22uF")
        (field (name "DB_TOLERANCE") "20%")
        (field (name "DB_VOLTAGE") "6.3V")
        (field (name "DB_MANUFACTURER_PART") "KEMET    C0805C226M9PAC")
        (field (name "DB_APPROVED_BY") "ISHIDDEN=T")
      )
      (libsource (lib "Database_Libs1") (part "C"))
    )
    (comp (ref "C661")
      (value "22uF")
      (footprint "SMD_0805_CAPC2012X145N")
      (fields
        (field (name "DB_PART_NUMBER") "CAP000043686")
        (field (name "DB_VALUE") "22uF")
        (field (name "DB_TOLERANCE") "20%")
        (field (name "DB_VOLTAGE") "6.3V")
        (field (name "DB_MANUFACTURER_PART") "KEMET    C0805C226M9PAC")
        (field (name "DB_APPROVED_BY") "ISHIDDEN=T")
      )
      (libsource (lib "Database_Libs1") (part "C"))
    )
    (comp (ref "C662")
      (value "220uF")
      (footprint "SMD_1210_CAPC3225X279N")
      (fields
        (field (name "DB_PART_NUMBER") "CAP000047355")
        (field (name "DB_VALUE") "220uF")
        (field (name "DB_TOLERANCE") "20%")
        (field (name "DB_VOLTAGE") "6.3V")
        (field (name "DB_MANUFACTURER_PART") "SAMSUNG    CL32A227MQVNNNE")
        (field (name "DB_APPROVED_BY") "VSN")
      )
      (libsource (lib "Database_Libs1") (part "C"))
    )
    (comp (ref "C663")
      (value "22uF")
      (footprint "SMD_0805_CAPC2012X145N")
      (fields
        (field (name "DB_PART_NUMBER") "CAP000043686")
        (field (name "DB_VALUE") "22uF")
        (field (name "DB_TOLERANCE") "20%")
        (field (name "DB_VOLTAGE") "6.3V")
        (field (name "DB_MANUFACTURER_PART") "KEMET    C0805C226M9PAC")
        (field (name "DB_APPROVED_BY") "ISHIDDEN=T")
      )
      (libsource (lib "Database_Libs1") (part "C"))
    )
    (comp (ref "C664")
      (value "22uF")
      (footprint "SMD_0805_CAPC2012X145N")
      (fields
        (field (name "DB_PART_NUMBER") "CAP000043686")
        (field (name "DB_VALUE") "22uF")
        (field (name "DB_TOLERANCE") "20%")
        (field (name "DB_VOLTAGE") "6.3V")
        (field (name "DB_MANUFACTURER_PART") "KEMET    C0805C226M9PAC")
        (field (name "DB_APPROVED_BY") "ISHIDDEN=T")
      )
      (libsource (lib "Database_Libs1") (part "C"))
    )
    (comp (ref "C665")
      (value "220uF")
      (footprint "SMD_1210_CAPC3225X279N")
      (fields
        (field (name "DB_PART_NUMBER") "CAP000047355")
        (field (name "DB_VALUE") "220uF")
        (field (name "DB_TOLERANCE") "20%")
        (field (name "DB_VOLTAGE") "6.3V")
        (field (name "DB_MANUFACTURER_PART") "SAMSUNG    CL32A227MQVNNNE")
        (field (name "DB_APPROVED_BY") "VSN")
      )
      (libsource (lib "Database_Libs1") (part "C"))
    )
    (comp (ref "C666")
      (value "22uF")
      (footprint "SMD_0805_CAPC2012X145N")
      (fields
        (field (name "DB_PART_NUMBER") "CAP000043686")
        (field (name "DB_VALUE") "22uF")
        (field (name "DB_TOLERANCE") "20%")
        (field (name "DB_VOLTAGE") "6.3V")
        (field (name "DB_MANUFACTURER_PART") "KEMET    C0805C226M9PAC")
        (field (name "DB_APPROVED_BY") "ISHIDDEN=T")
      )
      (libsource (lib "Database_Libs1") (part "C"))
    )
    (comp (ref "C667")
      (value "22uF")
      (footprint "SMD_0805_CAPC2012X145N")
      (fields
        (field (name "DB_PART_NUMBER") "CAP000043686")
        (field (name "DB_VALUE") "22uF")
        (field (name "DB_TOLERANCE") "20%")
        (field (name "DB_VOLTAGE") "6.3V")
        (field (name "DB_MANUFACTURER_PART") "KEMET    C0805C226M9PAC")
        (field (name "DB_APPROVED_BY") "ISHIDDEN=T")
      )
      (libsource (lib "Database_Libs1") (part "C"))
    )
    (comp (ref "C668")
      (value "220uF")
      (footprint "SMD_1210_CAPC3225X279N")
      (fields
        (field (name "DB_PART_NUMBER") "CAP000047355")
        (field (name "DB_VALUE") "220uF")
        (field (name "DB_TOLERANCE") "20%")
        (field (name "DB_VOLTAGE") "6.3V")
        (field (name "DB_MANUFACTURER_PART") "SAMSUNG    CL32A227MQVNNNE")
        (field (name "DB_APPROVED_BY") "VSN")
      )
      (libsource (lib "Database_Libs1") (part "C"))
    )
    (comp (ref "C669")
      (value "22uF")
      (footprint "SMD_0805_CAPC2012X145N")
      (fields
        (field (name "DB_PART_NUMBER") "CAP000043686")
        (field (name "DB_VALUE") "22uF")
        (field (name "DB_TOLERANCE") "20%")
        (field (name "DB_VOLTAGE") "6.3V")
        (field (name "DB_MANUFACTURER_PART") "KEMET    C0805C226M9PAC")
        (field (name "DB_APPROVED_BY") "ISHIDDEN=T")
      )
      (libsource (lib "Database_Libs1") (part "C"))
    )
    (comp (ref "C711")
      (value "10uF")
      (footprint "SMD_0805_CAPC2012X145N")
      (fields
        (field (name "DB_PART_NUMBER") "CAP000043636")
        (field (name "DB_VALUE") "10uF")
        (field (name "DB_TOLERANCE") "10%")
        (field (name "DB_VOLTAGE") "16V")
        (field (name "DB_MANUFACTURER_PART") "KEMET    C0805C106K4PAC")
        (field (name "DB_APPROVED_BY") "ISHIDDEN=T")
      )
      (libsource (lib "Database_Libs1") (part "C"))
    )
    (comp (ref "C814")
      (value "10uF")
      (footprint "SMD_0805_CAPC2012X145N")
      (fields
        (field (name "DB_PART_NUMBER") "CAP000043636")
        (field (name "DB_VALUE") "10uF")
        (field (name "DB_TOLERANCE") "10%")
        (field (name "DB_VOLTAGE") "16V")
        (field (name "DB_MANUFACTURER_PART") "KEMET    C0805C106K4PAC")
        (field (name "DB_APPROVED_BY") "ISHIDDEN=T")
      )
      (libsource (lib "Database_Libs1") (part "C"))
    )
    (comp (ref "L3")
      (value "~")
      (footprint "SMT_INDM135130X800N")
      (libsource (lib "EPIQ_DND_CIS_Library") (part "L"))
    )
    (comp (ref "L7")
      (value "~")
      (footprint "SMT_INDM135130X800N")
      (libsource (lib "EPIQ_DND_CIS_Library") (part "L"))
    )
    (comp (ref "L10")
      (value "~")
      (footprint "SMT_INDM135130X800N")
      (libsource (lib "EPIQ_DND_CIS_Library") (part "L"))
    )
    (comp (ref "L14")
      (value "~")
      (footprint "SMT_INDM135130X800N")
      (libsource (lib "EPIQ_DND_CIS_Library") (part "L"))
    )
    (comp (ref "R2")
      (value "10k")
      (footprint "SMD_0603_RESC1608X55N")
      (fields
        (field (name "DB_PART_NUMBER") "RES000008663")
        (field (name "DB_VALUE") "10k")
        (field (name "DB_TOLERANCE") "1%")
        (field (name "DB_MANUFACTURER_PART") "YAGEO    RC0603FR-0710KL")
        (field (name "DB_APPROVED_BY") "VSN")
      )
      (libsource (lib "Database_Libs1") (part "R"))
    )
    (comp (ref "R3")
      (value "100R")
      (footprint "SMD_0603_RESC1608X55N")
      (fields
        (field (name "DB_PART_NUMBER") "RES000006398")
        (field (name "DB_VALUE") "100R")
        (field (name "DB_TOLERANCE") "5%")
        (field (name "DB_MANUFACTURER_PART") "YAGEO    RC0603JR-07100R")
        (field (name "DB_APPROVED_BY") "ISHIDDEN=T")
      )
      (libsource (lib "Database_Libs1") (part "R"))
    )
    (comp (ref "R15")
      (value "10k")
      (footprint "SMD_0603_RESC1608X55N")
      (fields
        (field (name "DB_PART_NUMBER") "RES000008663")
        (field (name "DB_VALUE") "10k")
        (field (name "DB_TOLERANCE") "1%")
        (field (name "DB_MANUFACTURER_PART") "YAGEO    RC0603FR-0710KL")
        (field (name "DB_APPROVED_BY") "VSN")
      )
      (libsource (lib "Database_Libs1") (part "R"))
    )
    (comp (ref "R16")
      (value "100R")
      (footprint "SMD_0603_RESC1608X55N")
      (fields
        (field (name "DB_PART_NUMBER") "RES000006398")
        (field (name "DB_VALUE") "100R")
        (field (name "DB_TOLERANCE") "5%")
        (field (name "DB_MANUFACTURER_PART") "YAGEO    RC0603JR-07100R")
        (field (name "DB_APPROVED_BY") "ISHIDDEN=T")
      )
      (libsource (lib "Database_Libs1") (part "R"))
    )
    (comp (ref "R17")
      (value "10k")
      (footprint "SMD_0603_RESC1608X55N")
      (fields
        (field (name "DB_PART_NUMBER") "RES000008663")
        (field (name "DB_VALUE") "10k")
        (field (name "DB_TOLERANCE") "1%")
        (field (name "DB_MANUFACTURER_PART") "YAGEO    RC0603FR-0710KL")
        (field (name "DB_APPROVED_BY") "VSN")
      )
      (libsource (lib "Database_Libs1") (part "R"))
    )
    (comp (ref "R19")
      (value "100R")
      (footprint "SMD_0603_RESC1608X55N")
      (fields
        (field (name "DB_PART_NUMBER") "RES000006398")
        (field (name "DB_VALUE") "100R")
        (field (name "DB_TOLERANCE") "5%")
        (field (name "DB_MANUFACTURER_PART") "YAGEO    RC0603JR-07100R")
        (field (name "DB_APPROVED_BY") "ISHIDDEN=T")
      )
      (libsource (lib "Database_Libs1") (part "R"))
    )
    (comp (ref "R23")
      (value "10k")
      (footprint "SMD_0603_RESC1608X55N")
      (fields
        (field (name "DB_PART_NUMBER") "RES000008663")
        (field (name "DB_VALUE") "10k")
        (field (name "DB_TOLERANCE") "1%")
        (field (name "DB_MANUFACTURER_PART") "YAGEO    RC0603FR-0710KL")
        (field (name "DB_APPROVED_BY") "VSN")
      )
      (libsource (lib "Database_Libs1") (part "R"))
    )
    (comp (ref "R24")
      (value "100R")
      (footprint "SMD_0603_RESC1608X55N")
      (fields
        (field (name "DB_PART_NUMBER") "RES000006398")
        (field (name "DB_VALUE") "100R")
        (field (name "DB_TOLERANCE") "5%")
        (field (name "DB_MANUFACTURER_PART") "YAGEO    RC0603JR-07100R")
        (field (name "DB_APPROVED_BY") "ISHIDDEN=T")
      )
      (libsource (lib "Database_Libs1") (part "R"))
    )
    (comp (ref "TP4")
      (value "100_254")
      (footprint "SMD_TP_100-254")
      (fields
        (field (name "DB_PART_NUMBER") "TPO000000001")
        (field (name "DB_MANUFACTURER_PART") "ISHIDDEN=T")
        (field (name "DB_APPROVED_BY") "ISHIDDEN=T")
      )
      (libsource (lib "Database_Libs1") (part "TEST_POINT_1"))
    )
    (comp (ref "TP8")
      (value "100_254")
      (footprint "SMD_TP_100-254")
      (fields
        (field (name "DB_PART_NUMBER") "TPO000000001")
        (field (name "DB_MANUFACTURER_PART") "ISHIDDEN=T")
        (field (name "DB_APPROVED_BY") "ISHIDDEN=T")
      )
      (libsource (lib "Database_Libs1") (part "TEST_POINT_1"))
    )
    (comp (ref "TP9")
      (value "100_254")
      (footprint "SMD_TP_100-254")
      (fields
        (field (name "DB_PART_NUMBER") "TPO000000001")
        (field (name "DB_MANUFACTURER_PART") "ISHIDDEN=T")
        (field (name "DB_APPROVED_BY") "ISHIDDEN=T")
      )
      (libsource (lib "Database_Libs1") (part "TEST_POINT_1"))
    )
    (comp (ref "TP15")
      (value "100_254")
      (footprint "SMD_TP_100-254")
      (fields
        (field (name "DB_PART_NUMBER") "TPO000000001")
        (field (name "DB_MANUFACTURER_PART") "ISHIDDEN=T")
        (field (name "DB_APPROVED_BY") "ISHIDDEN=T")
      )
      (libsource (lib "Database_Libs1") (part "TEST_POINT_1"))
    )
    (comp (ref "TP16")
      (value "100_254")
      (footprint "SMD_TP_100-254")
      (fields
        (field (name "DB_PART_NUMBER") "TPO000000001")
        (field (name "DB_MANUFACTURER_PART") "ISHIDDEN=T")
        (field (name "DB_APPROVED_BY") "ISHIDDEN=T")
      )
      (libsource (lib "Database_Libs1") (part "TEST_POINT_1"))
    )
    (comp (ref "TP17")
      (value "100_254")
      (footprint "SMD_TP_100-254")
      (fields
        (field (name "DB_PART_NUMBER") "TPO000000001")
        (field (name "DB_MANUFACTURER_PART") "ISHIDDEN=T")
        (field (name "DB_APPROVED_BY") "ISHIDDEN=T")
      )
      (libsource (lib "Database_Libs1") (part "TEST_POINT_1"))
    )
    (comp (ref "TP26")
      (value "100_254")
      (footprint "SMD_TP_100-254")
      (fields
        (field (name "DB_PART_NUMBER") "TPO000000001")
        (field (name "DB_MANUFACTURER_PART") "ISHIDDEN=T")
        (field (name "DB_APPROVED_BY") "ISHIDDEN=T")
      )
      (libsource (lib "Database_Libs1") (part "TEST_POINT_1"))
    )
    (comp (ref "TP27")
      (value "100_254")
      (footprint "SMD_TP_100-254")
      (fields
        (field (name "DB_PART_NUMBER") "TPO000000001")
        (field (name "DB_MANUFACTURER_PART") "ISHIDDEN=T")
        (field (name "DB_APPROVED_BY") "ISHIDDEN=T")
      )
      (libsource (lib "Database_Libs1") (part "TEST_POINT_1"))
    )
    (comp (ref "U13")
      (value "~")
      (footprint "SMD_QFN50P600X600X80-43")
      (libsource (lib "BitCoin") (part "IC_SiC780"))
    )
    (comp (ref "U17")
      (value "~")
      (footprint "SMD_QFN50P600X600X80-43")
      (libsource (lib "BitCoin") (part "IC_SiC780"))
    )
    (comp (ref "U20")
      (value "~")
      (footprint "SMD_QFN50P600X600X80-43")
      (libsource (lib "BitCoin") (part "IC_SiC780"))
    )
    (comp (ref "U24")
      (value "~")
      (footprint "SMD_QFN50P600X600X80-43")
      (libsource (lib "BitCoin") (part "IC_SiC780"))
    )
  )
  (nets
    (net (code "1") (name "/1V") (class "Default")
      (node (ref "C128") (pin "1") (pinfunction "1_1") (pintype "passive"))
      (node (ref "C130") (pin "1") (pinfunction "1_1") (pintype "passive"))
      (node (ref "C131") (pin "1") (pinfunction "1_1") (pintype "passive"))
      (node (ref "C132") (pin "2") (pinfunction "2_2") (pintype "passive"))
      (node (ref "C138") (pin "1") (pinfunction "1_1") (pintype "passive"))
      (node (ref "C139") (pin "1") (pinfunction "1_1") (pintype "passive"))
      (node (ref "C140") (pin "2") (pinfunction "2_2") (pintype "passive"))
      (node (ref "C141") (pin "1") (pinfunction "1_1") (pintype "passive"))
      (node (ref "C142") (pin "1") (pinfunction "1_1") (pintype "passive"))
      (node (ref "C143") (pin "2") (pinfunction "2_2") (pintype "passive"))
      (node (ref "C144") (pin "1") (pinfunction "1_1") (pintype "passive"))
      (node (ref "C145") (pin "1") (pinfunction "1_1") (pintype "passive"))
      (node (ref "C146") (pin "2") (pinfunction "2_2") (pintype "passive"))
      (node (ref "C147") (pin "1") (pinfunction "1_1") (pintype "passive"))
      (node (ref "C166") (pin "1") (pinfunction "1_1") (pintype "passive"))
      (node (ref "C167") (pin "2") (pinfunction "2_2") (pintype "passive"))
      (node (ref "C169") (pin "1") (pinfunction "1_1") (pintype "passive"))
      (node (ref "C170") (pin "1") (pinfunction "1_1") (pintype "passive"))
      (node (ref "C172") (pin "1") (pinfunction "1_1") (pintype "passive"))
      (node (ref "C173") (pin "1") (pinfunction "1_1") (pintype "passive"))
      (node (ref "C174") (pin "2") (pinfunction "2_2") (pintype "passive"))
      (node (ref "C175") (pin "1") (pinfunction "1_1") (pintype "passive"))
      (node (ref "C176") (pin "1") (pinfunction "1_1") (pintype "passive"))
      (node (ref "C187") (pin "1") (pinfunction "1_1") (pintype "passive"))
      (node (ref "C188") (pin "1") (pinfunction "1_1") (pintype "passive"))
      (node (ref "C189") (pin "2") (pinfunction "2_2") (pintype "passive"))
      (node (ref "C190") (pin "1") (pinfunction "1_1") (pintype "passive"))
      (node (ref "C191") (pin "1") (pinfunction "1_1") (pintype "passive"))
      (node (ref "C192") (pin "2") (pinfunction "2_2") (pintype "passive"))
      (node (ref "C193") (pin "1") (pinfunction "1_1") (pintype "passive"))
      (node (ref "C194") (pin "1") (pinfunction "1_1") (pintype "passive"))
      (node (ref "C195") (pin "2") (pinfunction "2_2") (pintype "passive"))
      (node (ref "C196") (pin "1") (pinfunction "1_1") (pintype "passive"))
      (node (ref "C197") (pin "1") (pinfunction "1_1") (pintype "passive"))
      (node (ref "C199") (pin "1") (pinfunction "1_1") (pintype "passive"))
      (node (ref "C200") (pin "1") (pinfunction "1_1") (pintype "passive"))
      (node (ref "C202") (pin "1") (pinfunction "1_1") (pintype "passive"))
      (node (ref "C203") (pin "1") (pinfunction "1_1") (pintype "passive"))
      (node (ref "C205") (pin "1") (pinfunction "1_1") (pintype "passive"))
      (node (ref "C260") (pin "2") (pinfunction "2_2") (pintype "passive"))
      (node (ref "C261") (pin "2") (pinfunction "2_2") (pintype "passive"))
      (node (ref "C262") (pin "2") (pinfunction "2_2") (pintype "passive"))
      (node (ref "C263") (pin "1") (pinfunction "1_1") (pintype "passive"))
      (node (ref "C264") (pin "1") (pinfunction "1_1") (pintype "passive"))
      (node (ref "C265") (pin "1") (pinfunction "1_1") (pintype "passive"))
      (node (ref "C266") (pin "1") (pinfunction "1_1") (pintype "passive"))
      (node (ref "C267") (pin "2") (pinfunction "2_2") (pintype "passive"))
      (node (ref "C268") (pin "1") (pinfunction "1_1") (pintype "passive"))
      (node (ref "C269") (pin "1") (pinfunction "1_1") (pintype "passive"))
      (node (ref "C270") (pin "2") (pinfunction "2_2") (pintype "passive"))
      (node (ref "C271") (pin "1") (pinfunction "1_1") (pintype "passive"))
      (node (ref "C272") (pin "1") (pinfunction "1_1") (pintype "passive"))
      (node (ref "C273") (pin "2") (pinfunction "2_2") (pintype "passive"))
      (node (ref "C274") (pin "1") (pinfunction "1_1") (pintype "passive"))
      (node (ref "C275") (pin "1") (pinfunction "1_1") (pintype "passive"))
      (node (ref "C276") (pin "2") (pinfunction "2_2") (pintype "passive"))
      (node (ref "C331") (pin "1") (pinfunction "1_1") (pintype "passive"))
      (node (ref "C332") (pin "1") (pinfunction "1_1") (pintype "passive"))
      (node (ref "C333") (pin "1") (pinfunction "1_1") (pintype "passive"))
      (node (ref "C334") (pin "1") (pinfunction "1_1") (pintype "passive"))
      (node (ref "C37") (pin "1") (pinfunction "1_1") (pintype "passive"))
      (node (ref "C375") (pin "2") (pinfunction "2_2") (pintype "passive"))
      (node (ref "C376") (pin "2") (pinfunction "2_2") (pintype "passive"))
      (node (ref "C377") (pin "2") (pinfunction "2_2") (pintype "passive"))
      (node (ref "C38") (pin "1") (pinfunction "1_1") (pintype "passive"))
      (node (ref "C381") (pin "2") (pinfunction "2_2") (pintype "passive"))
      (node (ref "C382") (pin "2") (pinfunction "2_2") (pintype "passive"))
      (node (ref "C39") (pin "1") (pinfunction "1_1") (pintype "passive"))
      (node (ref "C397") (pin "2") (pinfunction "2_2") (pintype "passive"))
      (node (ref "C398") (pin "2") (pinfunction "2_2") (pintype "passive"))
      (node (ref "C399") (pin "2") (pinfunction "2_2") (pintype "passive"))
      (node (ref "C40") (pin "1") (pinfunction "1_1") (pintype "passive"))
      (node (ref "C400") (pin "2") (pinfunction "2_2") (pintype "passive"))
      (node (ref "C401") (pin "2") (pinfunction "2_2") (pintype "passive"))
      (node (ref "C65") (pin "1") (pinfunction "1_1") (pintype "passive"))
      (node (ref "C652") (pin "1") (pinfunction "1_1") (pintype "passive"))
      (node (ref "C653") (pin "2") (pinfunction "2_2") (pintype "passive"))
      (node (ref "C654") (pin "1") (pinfunction "1_1") (pintype "passive"))
      (node (ref "C655") (pin "1") (pinfunction "1_1") (pintype "passive"))
      (node (ref "C656") (pin "2") (pinfunction "2_2") (pintype "passive"))
      (node (ref "C657") (pin "1") (pinfunction "1_1") (pintype "passive"))
      (node (ref "C658") (pin "1") (pinfunction "1_1") (pintype "passive"))
      (node (ref "C659") (pin "2") (pinfunction "2_2") (pintype "passive"))
      (node (ref "C66") (pin "1") (pinfunction "1_1") (pintype "passive"))
      (node (ref "C660") (pin "1") (pinfunction "1_1") (pintype "passive"))
      (node (ref "C661") (pin "1") (pinfunction "1_1") (pintype "passive"))
      (node (ref "C662") (pin "2") (pinfunction "2_2") (pintype "passive"))
      (node (ref "C663") (pin "1") (pinfunction "1_1") (pintype "passive"))
      (node (ref "C664") (pin "1") (pinfunction "1_1") (pintype "passive"))
      (node (ref "C665") (pin "2") (pinfunction "2_2") (pintype "passive"))
      (node (ref "C666") (pin "1") (pinfunction "1_1") (pintype "passive"))
      (node (ref "C667") (pin "1") (pinfunction "1_1") (pintype "passive"))
      (node (ref "C668") (pin "2") (pinfunction "2_2") (pintype "passive"))
      (node (ref "C669") (pin "1") (pinfunction "1_1") (pintype "passive"))
      (node (ref "C67") (pin "1") (pinfunction "1_1") (pintype "passive"))
      (node (ref "C90") (pin "1") (pinfunction "1_1") (pintype "passive"))
      (node (ref "L10") (pin "2") (pinfunction "2_2") (pintype "passive"))
      (node (ref "L14") (pin "2") (pinfunction "2_2") (pintype "passive"))
      (node (ref "L3") (pin "2") (pinfunction "2_2") (pintype "passive"))
      (node (ref "L7") (pin "2") (pinfunction "2_2") (pintype "passive"))
    )
    (net (code "2") (name "/5.0V") (class "Default")
      (node (ref "C117") (pin "2") (pinfunction "2_2") (pintype "passive"))
      (node (ref "C22") (pin "2") (pinfunction "2_2") (pintype "passive"))
      (node (ref "C54") (pin "2") (pinfunction "2_2") (pintype "passive"))
      (node (ref "C85") (pin "2") (pinfunction "2_2") (pintype "passive"))
      (node (ref "R15") (pin "2") (pinfunction "2_2") (pintype "passive"))
      (node (ref "R16") (pin "1") (pinfunction "1_1") (pintype "passive"))
      (node (ref "R17") (pin "2") (pinfunction "2_2") (pintype "passive"))
      (node (ref "R19") (pin "1") (pinfunction "1_1") (pintype "passive"))
      (node (ref "R2") (pin "2") (pinfunction "2_2") (pintype "passive"))
      (node (ref "R23") (pin "2") (pinfunction "2_2") (pintype "passive"))
      (node (ref "R24") (pin "1") (pinfunction "1_1") (pintype "passive"))
      (node (ref "R3") (pin "1") (pinfunction "1_1") (pintype "passive"))
      (node (ref "U13") (pin "3") (pinfunction "VDRV_3") (pintype "passive"))
      (node (ref "U17") (pin "3") (pinfunction "VDRV_3") (pintype "passive"))
      (node (ref "U20") (pin "3") (pinfunction "VDRV_3") (pintype "passive"))
      (node (ref "U24") (pin "3") (pinfunction "VDRV_3") (pintype "passive"))
    )
    (net (code "3") (name "/12V") (class "Default")
      (node (ref "C100") (pin "1") (pinfunction "1_1") (pintype "passive"))
      (node (ref "C101") (pin "2") (pinfunction "2_2") (pintype "passive"))
      (node (ref "C102") (pin "2") (pinfunction "2_2") (pintype "passive"))
      (node (ref "C106") (pin "1") (pinfunction "1_1") (pintype "passive"))
      (node (ref "C107") (pin "2") (pinfunction "2_2") (pintype "passive"))
      (node (ref "C108") (pin "1") (pinfunction "1_1") (pintype "passive"))
      (node (ref "C109") (pin "1") (pinfunction "1_1") (pintype "passive"))
      (node (ref "C110") (pin "1") (pinfunction "1_1") (pintype "passive"))
      (node (ref "C111") (pin "1") (pinfunction "1_1") (pintype "passive"))
      (node (ref "C112") (pin "1") (pinfunction "1_1") (pintype "passive"))
      (node (ref "C113") (pin "1") (pinfunction "1_1") (pintype "passive"))
      (node (ref "C114") (pin "1") (pinfunction "1_1") (pintype "passive"))
      (node (ref "C115") (pin "1") (pinfunction "1_1") (pintype "passive"))
      (node (ref "C116") (pin "1") (pinfunction "1_1") (pintype "passive"))
      (node (ref "C118") (pin "1") (pinfunction "1_1") (pintype "passive"))
      (node (ref "C119") (pin "1") (pinfunction "1_1") (pintype "passive"))
      (node (ref "C120") (pin "1") (pinfunction "1_1") (pintype "passive"))
      (node (ref "C122") (pin "1") (pinfunction "1_1") (pintype "passive"))
      (node (ref "C123") (pin "1") (pinfunction "1_1") (pintype "passive"))
      (node (ref "C124") (pin "1") (pinfunction "1_1") (pintype "passive"))
      (node (ref "C126") (pin "1") (pinfunction "1_1") (pintype "passive"))
      (node (ref "C127") (pin "1") (pinfunction "1_1") (pintype "passive"))
      (node (ref "C133") (pin "2") (pinfunction "2_2") (pintype "passive"))
      (node (ref "C134") (pin "2") (pinfunction "2_2") (pintype "passive"))
      (node (ref "C20") (pin "1") (pinfunction "1_1") (pintype "passive"))
      (node (ref "C21") (pin "1") (pinfunction "1_1") (pintype "passive"))
      (node (ref "C23") (pin "1") (pinfunction "1_1") (pintype "passive"))
      (node (ref "C24") (pin "1") (pinfunction "1_1") (pintype "passive"))
      (node (ref "C25") (pin "1") (pinfunction "1_1") (pintype "passive"))
      (node (ref "C258") (pin "2") (pinfunction "2_2") (pintype "passive"))
      (node (ref "C259") (pin "2") (pinfunction "2_2") (pintype "passive"))
      (node (ref "C373") (pin "2") (pinfunction "2_2") (pintype "passive"))
      (node (ref "C374") (pin "2") (pinfunction "2_2") (pintype "passive"))
      (node (ref "C378") (pin "1") (pinfunction "1_1") (pintype "passive"))
      (node (ref "C379") (pin "1") (pinfunction "1_1") (pintype "passive"))
      (node (ref "C380") (pin "1") (pinfunction "1_1") (pintype "passive"))
      (node (ref "C404") (pin "2") (pinfunction "2_2") (pintype "passive"))
      (node (ref "C405") (pin "2") (pinfunction "2_2") (pintype "passive"))
      (node (ref "C406") (pin "2") (pinfunction "2_2") (pintype "passive"))
      (node (ref "C407") (pin "2") (pinfunction "2_2") (pintype "passive"))
      (node (ref "C41") (pin "2") (pinfunction "2_2") (pintype "passive"))
      (node (ref "C42") (pin "2") (pinfunction "2_2") (pintype "passive"))
      (node (ref "C43") (pin "2") (pinfunction "2_2") (pintype "passive"))
      (node (ref "C47") (pin "2") (pinfunction "2_2") (pintype "passive"))
      (node (ref "C49") (pin "1") (pinfunction "1_1") (pintype "passive"))
      (node (ref "C50") (pin "1") (pinfunction "1_1") (pintype "passive"))
      (node (ref "C51") (pin "1") (pinfunction "1_1") (pintype "passive"))
      (node (ref "C52") (pin "1") (pinfunction "1_1") (pintype "passive"))
      (node (ref "C596") (pin "2") (pinfunction "2_2") (pintype "passive"))
      (node (ref "C598") (pin "1") (pinfunction "1_1") (pintype "passive"))
      (node (ref "C599") (pin "2") (pinfunction "2_2") (pintype "passive"))
      (node (ref "C600") (pin "1") (pinfunction "1_1") (pintype "passive"))
      (node (ref "C602") (pin "2") (pinfunction "2_2") (pintype "passive"))
      (node (ref "C603") (pin "1") (pinfunction "1_1") (pintype "passive"))
      (node (ref "C605") (pin "2") (pinfunction "2_2") (pintype "passive"))
      (node (ref "C606") (pin "1") (pinfunction "1_1") (pintype "passive"))
      (node (ref "C640") (pin "1") (pinfunction "1_1") (pintype "passive"))
      (node (ref "C642") (pin "1") (pinfunction "1_1") (pintype "passive"))
      (node (ref "C68") (pin "1") (pinfunction "1_1") (pintype "passive"))
      (node (ref "C69") (pin "1") (pinfunction "1_1") (pintype "passive"))
      (node (ref "C70") (pin "1") (pinfunction "1_1") (pintype "passive"))
      (node (ref "C71") (pin "1") (pinfunction "1_1") (pintype "passive"))
      (node (ref "C711") (pin "1") (pinfunction "1_1") (pintype "passive"))
      (node (ref "C814") (pin "1") (pinfunction "1_1") (pintype "passive"))
      (node (ref "C91") (pin "1") (pinfunction "1_1") (pintype "passive"))
      (node (ref "C92") (pin "2") (pinfunction "2_2") (pintype "passive"))
      (node (ref "C94") (pin "1") (pinfunction "1_1") (pintype "passive"))
      (node (ref "C95") (pin "1") (pinfunction "1_1") (pintype "passive"))
      (node (ref "C96") (pin "2") (pinfunction "2_2") (pintype "passive"))
      (node (ref "C97") (pin "1") (pinfunction "1_1") (pintype "passive"))
      (node (ref "C98") (pin "1") (pinfunction "1_1") (pintype "passive"))
      (node (ref "C99") (pin "2") (pinfunction "2_2") (pintype "passive"))
      (node (ref "U13") (pin "10") (pinfunction "VIN_10") (pintype "passive"))
      (node (ref "U13") (pin "11") (pinfunction "VIN_11") (pintype "passive"))
      (node (ref "U13") (pin "12") (pinfunction "VIN_12") (pintype "passive"))
      (node (ref "U13") (pin "13") (pinfunction "VIN_13") (pintype "passive"))
      (node (ref "U13") (pin "14") (pinfunction "VIN_14") (pintype "passive"))
      (node (ref "U13") (pin "42") (pinfunction "VIN_42") (pintype "passive"))
      (node (ref "U13") (pin "8") (pinfunction "VIN_8") (pintype "passive"))
      (node (ref "U13") (pin "9") (pinfunction "VIN_9") (pintype "passive"))
      (node (ref "U17") (pin "10") (pinfunction "VIN_10") (pintype "passive"))
      (node (ref "U17") (pin "11") (pinfunction "VIN_11") (pintype "passive"))
      (node (ref "U17") (pin "12") (pinfunction "VIN_12") (pintype "passive"))
      (node (ref "U17") (pin "13") (pinfunction "VIN_13") (pintype "passive"))
      (node (ref "U17") (pin "14") (pinfunction "VIN_14") (pintype "passive"))
      (node (ref "U17") (pin "42") (pinfunction "VIN_42") (pintype "passive"))
      (node (ref "U17") (pin "8") (pinfunction "VIN_8") (pintype "passive"))
      (node (ref "U17") (pin "9") (pinfunction "VIN_9") (pintype "passive"))
      (node (ref "U20") (pin "10") (pinfunction "VIN_10") (pintype "passive"))
      (node (ref "U20") (pin "11") (pinfunction "VIN_11") (pintype "passive"))
      (node (ref "U20") (pin "12") (pinfunction "VIN_12") (pintype "passive"))
      (node (ref "U20") (pin "13") (pinfunction "VIN_13") (pintype "passive"))
      (node (ref "U20") (pin "14") (pinfunction "VIN_14") (pintype "passive"))
      (node (ref "U20") (pin "42") (pinfunction "VIN_42") (pintype "passive"))
      (node (ref "U20") (pin "8") (pinfunction "VIN_8") (pintype "passive"))
      (node (ref "U20") (pin "9") (pinfunction "VIN_9") (pintype "passive"))
      (node (ref "U24") (pin "10") (pinfunction "VIN_10") (pintype "passive"))
      (node (ref "U24") (pin "11") (pinfunction "VIN_11") (pintype "passive"))
      (node (ref "U24") (pin "12") (pinfunction "VIN_12") (pintype "passive"))
      (node (ref "U24") (pin "13") (pinfunction "VIN_13") (pintype "passive"))
      (node (ref "U24") (pin "14") (pinfunction "VIN_14") (pintype "passive"))
      (node (ref "U24") (pin "42") (pinfunction "VIN_42") (pintype "passive"))
      (node (ref "U24") (pin "8") (pinfunction "VIN_8") (pintype "passive"))
      (node (ref "U24") (pin "9") (pinfunction "VIN_9") (pintype "passive"))
    )
    (net (code "4") (name "/PWM1L") (class "Default")
      (node (ref "U13") (pin "40") (pinfunction "PWM_40") (pintype "passive"))
    )
    (net (code "5") (name "/PWM2L") (class "Default")
      (node (ref "U17") (pin "40") (pinfunction "PWM_40") (pintype "passive"))
    )
    (net (code "6") (name "/PWM3H") (class "Default")
      (node (ref "U20") (pin "40") (pinfunction "PWM_40") (pintype "passive"))
    )
    (net (code "7") (name "/PWM4H") (class "Default")
      (node (ref "U24") (pin "40") (pinfunction "PWM_40") (pintype "passive"))
    )
    (net (code "8") (name "/SWN7") (class "Default")
      (node (ref "L10") (pin "1") (pinfunction "1_1") (pintype "passive"))
      (node (ref "U20") (pin "15") (pinfunction "VSWH_15") (pintype "passive"))
      (node (ref "U20") (pin "29") (pinfunction "VSWH_29") (pintype "passive"))
      (node (ref "U20") (pin "30") (pinfunction "VSWH_30") (pintype "passive"))
      (node (ref "U20") (pin "31") (pinfunction "VSWH_31") (pintype "passive"))
      (node (ref "U20") (pin "32") (pinfunction "VSWH_32") (pintype "passive"))
      (node (ref "U20") (pin "33") (pinfunction "VSWH_33") (pintype "passive"))
      (node (ref "U20") (pin "34") (pinfunction "VSWH_34") (pintype "passive"))
      (node (ref "U20") (pin "35") (pinfunction "VSWH_35") (pintype "passive"))
      (node (ref "U20") (pin "43") (pinfunction "VSWH_43") (pintype "passive"))
    )
    (net (code "9") (name "/SWN8") (class "Default")
      (node (ref "L14") (pin "1") (pinfunction "1_1") (pintype "passive"))
      (node (ref "U24") (pin "15") (pinfunction "VSWH_15") (pintype "passive"))
      (node (ref "U24") (pin "29") (pinfunction "VSWH_29") (pintype "passive"))
      (node (ref "U24") (pin "30") (pinfunction "VSWH_30") (pintype "passive"))
      (node (ref "U24") (pin "31") (pinfunction "VSWH_31") (pintype "passive"))
      (node (ref "U24") (pin "32") (pinfunction "VSWH_32") (pintype "passive"))
      (node (ref "U24") (pin "33") (pinfunction "VSWH_33") (pintype "passive"))
      (node (ref "U24") (pin "34") (pinfunction "VSWH_34") (pintype "passive"))
      (node (ref "U24") (pin "35") (pinfunction "VSWH_35") (pintype "passive"))
      (node (ref "U24") (pin "43") (pinfunction "VSWH_43") (pintype "passive"))
    )
    (net (code "10") (name "/SWN9") (class "Default")
      (node (ref "L3") (pin "1") (pinfunction "1_1") (pintype "passive"))
      (node (ref "U13") (pin "15") (pinfunction "VSWH_15") (pintype "passive"))
      (node (ref "U13") (pin "29") (pinfunction "VSWH_29") (pintype "passive"))
      (node (ref "U13") (pin "30") (pinfunction "VSWH_30") (pintype "passive"))
      (node (ref "U13") (pin "31") (pinfunction "VSWH_31") (pintype "passive"))
      (node (ref "U13") (pin "32") (pinfunction "VSWH_32") (pintype "passive"))
      (node (ref "U13") (pin "33") (pinfunction "VSWH_33") (pintype "passive"))
      (node (ref "U13") (pin "34") (pinfunction "VSWH_34") (pintype "passive"))
      (node (ref "U13") (pin "35") (pinfunction "VSWH_35") (pintype "passive"))
      (node (ref "U13") (pin "43") (pinfunction "VSWH_43") (pintype "passive"))
    )
    (net (code "11") (name "/SWN10") (class "Default")
      (node (ref "L7") (pin "1") (pinfunction "1_1") (pintype "passive"))
      (node (ref "U17") (pin "15") (pinfunction "VSWH_15") (pintype "passive"))
      (node (ref "U17") (pin "29") (pinfunction "VSWH_29") (pintype "passive"))
      (node (ref "U17") (pin "30") (pinfunction "VSWH_30") (pintype "passive"))
      (node (ref "U17") (pin "31") (pinfunction "VSWH_31") (pintype "passive"))
      (node (ref "U17") (pin "32") (pinfunction "VSWH_32") (pintype "passive"))
      (node (ref "U17") (pin "33") (pinfunction "VSWH_33") (pintype "passive"))
      (node (ref "U17") (pin "34") (pinfunction "VSWH_34") (pintype "passive"))
      (node (ref "U17") (pin "35") (pinfunction "VSWH_35") (pintype "passive"))
      (node (ref "U17") (pin "43") (pinfunction "VSWH_43") (pintype "passive"))
    )
    (net (code "12") (name "/THDN") (class "Default")
      (node (ref "U13") (pin "38") (pinfunction "THDN_38") (pintype "passive"))
      (node (ref "U17") (pin "38") (pinfunction "THDN_38") (pintype "passive"))
      (node (ref "U20") (pin "38") (pinfunction "THDN_38") (pintype "passive"))
      (node (ref "U24") (pin "38") (pinfunction "THDN_38") (pintype "passive"))
    )
    (net (code "13") (name "GND") (class "Default")
      (node (ref "C100") (pin "2") (pinfunction "2_2") (pintype "passive"))
      (node (ref "C101") (pin "1") (pinfunction "1_1") (pintype "passive"))
      (node (ref "C102") (pin "1") (pinfunction "1_1") (pintype "passive"))
      (node (ref "C106") (pin "2") (pinfunction "2_2") (pintype "passive"))
      (node (ref "C107") (pin "1") (pinfunction "1_1") (pintype "passive"))
      (node (ref "C108") (pin "2") (pinfunction "2_2") (pintype "passive"))
      (node (ref "C109") (pin "2") (pinfunction "2_2") (pintype "passive"))
      (node (ref "C110") (pin "2") (pinfunction "2_2") (pintype "passive"))
      (node (ref "C111") (pin "2") (pinfunction "2_2") (pintype "passive"))
      (node (ref "C112") (pin "2") (pinfunction "2_2") (pintype "passive"))
      (node (ref "C113") (pin "2") (pinfunction "2_2") (pintype "passive"))
      (node (ref "C114") (pin "2") (pinfunction "2_2") (pintype "passive"))
      (node (ref "C115") (pin "2") (pinfunction "2_2") (pintype "passive"))
      (node (ref "C116") (pin "2") (pinfunction "2_2") (pintype "passive"))
      (node (ref "C117") (pin "1") (pinfunction "1_1") (pintype "passive"))
      (node (ref "C118") (pin "2") (pinfunction "2_2") (pintype "passive"))
      (node (ref "C119") (pin "2") (pinfunction "2_2") (pintype "passive"))
      (node (ref "C120") (pin "2") (pinfunction "2_2") (pintype "passive"))
      (node (ref "C121") (pin "2") (pinfunction "2_2") (pintype "passive"))
      (node (ref "C122") (pin "2") (pinfunction "2_2") (pintype "passive"))
      (node (ref "C123") (pin "2") (pinfunction "2_2") (pintype "passive"))
      (node (ref "C124") (pin "2") (pinfunction "2_2") (pintype "passive"))
      (node (ref "C126") (pin "2") (pinfunction "2_2") (pintype "passive"))
      (node (ref "C127") (pin "2") (pinfunction "2_2") (pintype "passive"))
      (node (ref "C128") (pin "2") (pinfunction "2_2") (pintype "passive"))
      (node (ref "C130") (pin "2") (pinfunction "2_2") (pintype "passive"))
      (node (ref "C131") (pin "2") (pinfunction "2_2") (pintype "passive"))
      (node (ref "C132") (pin "1") (pinfunction "1_1") (pintype "passive"))
      (node (ref "C133") (pin "1") (pinfunction "1_1") (pintype "passive"))
      (node (ref "C134") (pin "1") (pinfunction "1_1") (pintype "passive"))
      (node (ref "C138") (pin "2") (pinfunction "2_2") (pintype "passive"))
      (node (ref "C139") (pin "2") (pinfunction "2_2") (pintype "passive"))
      (node (ref "C140") (pin "1") (pinfunction "1_1") (pintype "passive"))
      (node (ref "C141") (pin "2") (pinfunction "2_2") (pintype "passive"))
      (node (ref "C142") (pin "2") (pinfunction "2_2") (pintype "passive"))
      (node (ref "C143") (pin "1") (pinfunction "1_1") (pintype "passive"))
      (node (ref "C144") (pin "2") (pinfunction "2_2") (pintype "passive"))
      (node (ref "C145") (pin "2") (pinfunction "2_2") (pintype "passive"))
      (node (ref "C146") (pin "1") (pinfunction "1_1") (pintype "passive"))
      (node (ref "C147") (pin "2") (pinfunction "2_2") (pintype "passive"))
      (node (ref "C166") (pin "2") (pinfunction "2_2") (pintype "passive"))
      (node (ref "C167") (pin "1") (pinfunction "1_1") (pintype "passive"))
      (node (ref "C169") (pin "2") (pinfunction "2_2") (pintype "passive"))
      (node (ref "C170") (pin "2") (pinfunction "2_2") (pintype "passive"))
      (node (ref "C172") (pin "2") (pinfunction "2_2") (pintype "passive"))
      (node (ref "C173") (pin "2") (pinfunction "2_2") (pintype "passive"))
      (node (ref "C174") (pin "1") (pinfunction "1_1") (pintype "passive"))
      (node (ref "C175") (pin "2") (pinfunction "2_2") (pintype "passive"))
      (node (ref "C176") (pin "2") (pinfunction "2_2") (pintype "passive"))
      (node (ref "C187") (pin "2") (pinfunction "2_2") (pintype "passive"))
      (node (ref "C188") (pin "2") (pinfunction "2_2") (pintype "passive"))
      (node (ref "C189") (pin "1") (pinfunction "1_1") (pintype "passive"))
      (node (ref "C190") (pin "2") (pinfunction "2_2") (pintype "passive"))
      (node (ref "C191") (pin "2") (pinfunction "2_2") (pintype "passive"))
      (node (ref "C192") (pin "1") (pinfunction "1_1") (pintype "passive"))
      (node (ref "C193") (pin "2") (pinfunction "2_2") (pintype "passive"))
      (node (ref "C194") (pin "2") (pinfunction "2_2") (pintype "passive"))
      (node (ref "C195") (pin "1") (pinfunction "1_1") (pintype "passive"))
      (node (ref "C196") (pin "2") (pinfunction "2_2") (pintype "passive"))
      (node (ref "C197") (pin "2") (pinfunction "2_2") (pintype "passive"))
      (node (ref "C199") (pin "2") (pinfunction "2_2") (pintype "passive"))
      (node (ref "C20") (pin "2") (pinfunction "2_2") (pintype "passive"))
      (node (ref "C200") (pin "2") (pinfunction "2_2") (pintype "passive"))
      (node (ref "C202") (pin "2") (pinfunction "2_2") (pintype "passive"))
      (node (ref "C203") (pin "2") (pinfunction "2_2") (pintype "passive"))
      (node (ref "C205") (pin "2") (pinfunction "2_2") (pintype "passive"))
      (node (ref "C21") (pin "2") (pinfunction "2_2") (pintype "passive"))
      (node (ref "C22") (pin "1") (pinfunction "1_1") (pintype "passive"))
      (node (ref "C23") (pin "2") (pinfunction "2_2") (pintype "passive"))
      (node (ref "C24") (pin "2") (pinfunction "2_2") (pintype "passive"))
      (node (ref "C25") (pin "2") (pinfunction "2_2") (pintype "passive"))
      (node (ref "C258") (pin "1") (pinfunction "1_1") (pintype "passive"))
      (node (ref "C259") (pin "1") (pinfunction "1_1") (pintype "passive"))
      (node (ref "C26") (pin "2") (pinfunction "2_2") (pintype "passive"))
      (node (ref "C260") (pin "1") (pinfunction "1_1") (pintype "passive"))
      (node (ref "C261") (pin "1") (pinfunction "1_1") (pintype "passive"))
      (node (ref "C262") (pin "1") (pinfunction "1_1") (pintype "passive"))
      (node (ref "C263") (pin "2") (pinfunction "2_2") (pintype "passive"))
      (node (ref "C264") (pin "2") (pinfunction "2_2") (pintype "passive"))
      (node (ref "C265") (pin "2") (pinfunction "2_2") (pintype "passive"))
      (node (ref "C266") (pin "2") (pinfunction "2_2") (pintype "passive"))
      (node (ref "C267") (pin "1") (pinfunction "1_1") (pintype "passive"))
      (node (ref "C268") (pin "2") (pinfunction "2_2") (pintype "passive"))
      (node (ref "C269") (pin "2") (pinfunction "2_2") (pintype "passive"))
      (node (ref "C270") (pin "1") (pinfunction "1_1") (pintype "passive"))
      (node (ref "C271") (pin "2") (pinfunction "2_2") (pintype "passive"))
      (node (ref "C272") (pin "2") (pinfunction "2_2") (pintype "passive"))
      (node (ref "C273") (pin "1") (pinfunction "1_1") (pintype "passive"))
      (node (ref "C274") (pin "2") (pinfunction "2_2") (pintype "passive"))
      (node (ref "C275") (pin "2") (pinfunction "2_2") (pintype "passive"))
      (node (ref "C276") (pin "1") (pinfunction "1_1") (pintype "passive"))
      (node (ref "C331") (pin "2") (pinfunction "2_2") (pintype "passive"))
      (node (ref "C332") (pin "2") (pinfunction "2_2") (pintype "passive"))
      (node (ref "C333") (pin "2") (pinfunction "2_2") (pintype "passive"))
      (node (ref "C334") (pin "2") (pinfunction "2_2") (pintype "passive"))
      (node (ref "C37") (pin "2") (pinfunction "2_2") (pintype "passive"))
      (node (ref "C373") (pin "1") (pinfunction "1_1") (pintype "passive"))
      (node (ref "C374") (pin "1") (pinfunction "1_1") (pintype "passive"))
      (node (ref "C375") (pin "1") (pinfunction "1_1") (pintype "passive"))
      (node (ref "C376") (pin "1") (pinfunction "1_1") (pintype "passive"))
      (node (ref "C377") (pin "1") (pinfunction "1_1") (pintype "passive"))
      (node (ref "C378") (pin "2") (pinfunction "2_2") (pintype "passive"))
      (node (ref "C379") (pin "2") (pinfunction "2_2") (pintype "passive"))
      (node (ref "C38") (pin "2") (pinfunction "2_2") (pintype "passive"))
      (node (ref "C380") (pin "2") (pinfunction "2_2") (pintype "passive"))
      (node (ref "C381") (pin "1") (pinfunction "1_1") (pintype "passive"))
      (node (ref "C382") (pin "1") (pinfunction "1_1") (pintype "passive"))
      (node (ref "C39") (pin "2") (pinfunction "2_2") (pintype "passive"))
      (node (ref "C397") (pin "1") (pinfunction "1_1") (pintype "passive"))
      (node (ref "C398") (pin "1") (pinfunction "1_1") (pintype "passive"))
      (node (ref "C399") (pin "1") (pinfunction "1_1") (pintype "passive"))
      (node (ref "C40") (pin "2") (pinfunction "2_2") (pintype "passive"))
      (node (ref "C400") (pin "1") (pinfunction "1_1") (pintype "passive"))
      (node (ref "C401") (pin "1") (pinfunction "1_1") (pintype "passive"))
      (node (ref "C404") (pin "1") (pinfunction "1_1") (pintype "passive"))
      (node (ref "C405") (pin "1") (pinfunction "1_1") (pintype "passive"))
      (node (ref "C406") (pin "1") (pinfunction "1_1") (pintype "passive"))
      (node (ref "C407") (pin "1") (pinfunction "1_1") (pintype "passive"))
      (node (ref "C41") (pin "1") (pinfunction "1_1") (pintype "passive"))
      (node (ref "C42") (pin "1") (pinfunction "1_1") (pintype "passive"))
      (node (ref "C43") (pin "1") (pinfunction "1_1") (pintype "passive"))
      (node (ref "C47") (pin "1") (pinfunction "1_1") (pintype "passive"))
      (node (ref "C49") (pin "2") (pinfunction "2_2") (pintype "passive"))
      (node (ref "C50") (pin "2") (pinfunction "2_2") (pintype "passive"))
      (node (ref "C51") (pin "2") (pinfunction "2_2") (pintype "passive"))
      (node (ref "C52") (pin "2") (pinfunction "2_2") (pintype "passive"))
      (node (ref "C54") (pin "1") (pinfunction "1_1") (pintype "passive"))
      (node (ref "C58") (pin "2") (pinfunction "2_2") (pintype "passive"))
      (node (ref "C596") (pin "1") (pinfunction "1_1") (pintype "passive"))
      (node (ref "C598") (pin "2") (pinfunction "2_2") (pintype "passive"))
      (node (ref "C599") (pin "1") (pinfunction "1_1") (pintype "passive"))
      (node (ref "C600") (pin "2") (pinfunction "2_2") (pintype "passive"))
      (node (ref "C602") (pin "1") (pinfunction "1_1") (pintype "passive"))
      (node (ref "C603") (pin "2") (pinfunction "2_2") (pintype "passive"))
      (node (ref "C605") (pin "1") (pinfunction "1_1") (pintype "passive"))
      (node (ref "C606") (pin "2") (pinfunction "2_2") (pintype "passive"))
      (node (ref "C640") (pin "2") (pinfunction "2_2") (pintype "passive"))
      (node (ref "C642") (pin "2") (pinfunction "2_2") (pintype "passive"))
      (node (ref "C65") (pin "2") (pinfunction "2_2") (pintype "passive"))
      (node (ref "C652") (pin "2") (pinfunction "2_2") (pintype "passive"))
      (node (ref "C653") (pin "1") (pinfunction "1_1") (pintype "passive"))
      (node (ref "C654") (pin "2") (pinfunction "2_2") (pintype "passive"))
      (node (ref "C655") (pin "2") (pinfunction "2_2") (pintype "passive"))
      (node (ref "C656") (pin "1") (pinfunction "1_1") (pintype "passive"))
      (node (ref "C657") (pin "2") (pinfunction "2_2") (pintype "passive"))
      (node (ref "C658") (pin "2") (pinfunction "2_2") (pintype "passive"))
      (node (ref "C659") (pin "1") (pinfunction "1_1") (pintype "passive"))
      (node (ref "C66") (pin "2") (pinfunction "2_2") (pintype "passive"))
      (node (ref "C660") (pin "2") (pinfunction "2_2") (pintype "passive"))
      (node (ref "C661") (pin "2") (pinfunction "2_2") (pintype "passive"))
      (node (ref "C662") (pin "1") (pinfunction "1_1") (pintype "passive"))
      (node (ref "C663") (pin "2") (pinfunction "2_2") (pintype "passive"))
      (node (ref "C664") (pin "2") (pinfunction "2_2") (pintype "passive"))
      (node (ref "C665") (pin "1") (pinfunction "1_1") (pintype "passive"))
      (node (ref "C666") (pin "2") (pinfunction "2_2") (pintype "passive"))
      (node (ref "C667") (pin "2") (pinfunction "2_2") (pintype "passive"))
      (node (ref "C668") (pin "1") (pinfunction "1_1") (pintype "passive"))
      (node (ref "C669") (pin "2") (pinfunction "2_2") (pintype "passive"))
      (node (ref "C67") (pin "2") (pinfunction "2_2") (pintype "passive"))
      (node (ref "C68") (pin "2") (pinfunction "2_2") (pintype "passive"))
      (node (ref "C69") (pin "2") (pinfunction "2_2") (pintype "passive"))
      (node (ref "C70") (pin "2") (pinfunction "2_2") (pintype "passive"))
      (node (ref "C71") (pin "2") (pinfunction "2_2") (pintype "passive"))
      (node (ref "C711") (pin "2") (pinfunction "2_2") (pintype "passive"))
      (node (ref "C814") (pin "2") (pinfunction "2_2") (pintype "passive"))
      (node (ref "C85") (pin "1") (pinfunction "1_1") (pintype "passive"))
      (node (ref "C89") (pin "2") (pinfunction "2_2") (pintype "passive"))
      (node (ref "C90") (pin "2") (pinfunction "2_2") (pintype "passive"))
      (node (ref "C91") (pin "2") (pinfunction "2_2") (pintype "passive"))
      (node (ref "C92") (pin "1") (pinfunction "1_1") (pintype "passive"))
      (node (ref "C94") (pin "2") (pinfunction "2_2") (pintype "passive"))
      (node (ref "C95") (pin "2") (pinfunction "2_2") (pintype "passive"))
      (node (ref "C96") (pin "1") (pinfunction "1_1") (pintype "passive"))
      (node (ref "C97") (pin "2") (pinfunction "2_2") (pintype "passive"))
      (node (ref "C98") (pin "2") (pinfunction "2_2") (pintype "passive"))
      (node (ref "C99") (pin "1") (pinfunction "1_1") (pintype "passive"))
      (node (ref "U13") (pin "16") (pinfunction "PGND_16") (pintype "passive"))
      (node (ref "U13") (pin "17") (pinfunction "PGND_17") (pintype "passive"))
      (node (ref "U13") (pin "18") (pinfunction "PGND_18") (pintype "passive"))
      (node (ref "U13") (pin "19") (pinfunction "PGND_19") (pintype "passive"))
      (node (ref "U13") (pin "20") (pinfunction "PGND_20") (pintype "passive"))
      (node (ref "U13") (pin "21") (pinfunction "PGND_21") (pintype "passive"))
      (node (ref "U13") (pin "22") (pinfunction "PGND_22") (pintype "passive"))
      (node (ref "U13") (pin "23") (pinfunction "PGND_23") (pintype "passive"))
      (node (ref "U13") (pin "24") (pinfunction "PGND_24") (pintype "passive"))
      (node (ref "U13") (pin "25") (pinfunction "PGND_25") (pintype "passive"))
      (node (ref "U13") (pin "26") (pinfunction "PGND_26") (pintype "passive"))
      (node (ref "U13") (pin "27") (pinfunction "PGND_27") (pintype "passive"))
      (node (ref "U13") (pin "28") (pinfunction "PGND_28") (pintype "passive"))
      (node (ref "U13") (pin "37") (pinfunction "CGND_37") (pintype "passive"))
      (node (ref "U13") (pin "41") (pinfunction "CGND_41") (pintype "passive"))
      (node (ref "U13") (pin "5") (pinfunction "CGND_5") (pintype "passive"))
      (node (ref "U17") (pin "16") (pinfunction "PGND_16") (pintype "passive"))
      (node (ref "U17") (pin "17") (pinfunction "PGND_17") (pintype "passive"))
      (node (ref "U17") (pin "18") (pinfunction "PGND_18") (pintype "passive"))
      (node (ref "U17") (pin "19") (pinfunction "PGND_19") (pintype "passive"))
      (node (ref "U17") (pin "20") (pinfunction "PGND_20") (pintype "passive"))
      (node (ref "U17") (pin "21") (pinfunction "PGND_21") (pintype "passive"))
      (node (ref "U17") (pin "22") (pinfunction "PGND_22") (pintype "passive"))
      (node (ref "U17") (pin "23") (pinfunction "PGND_23") (pintype "passive"))
      (node (ref "U17") (pin "24") (pinfunction "PGND_24") (pintype "passive"))
      (node (ref "U17") (pin "25") (pinfunction "PGND_25") (pintype "passive"))
      (node (ref "U17") (pin "26") (pinfunction "PGND_26") (pintype "passive"))
      (node (ref "U17") (pin "27") (pinfunction "PGND_27") (pintype "passive"))
      (node (ref "U17") (pin "28") (pinfunction "PGND_28") (pintype "passive"))
      (node (ref "U17") (pin "37") (pinfunction "CGND_37") (pintype "passive"))
      (node (ref "U17") (pin "41") (pinfunction "CGND_41") (pintype "passive"))
      (node (ref "U17") (pin "5") (pinfunction "CGND_5") (pintype "passive"))
      (node (ref "U20") (pin "16") (pinfunction "PGND_16") (pintype "passive"))
      (node (ref "U20") (pin "17") (pinfunction "PGND_17") (pintype "passive"))
      (node (ref "U20") (pin "18") (pinfunction "PGND_18") (pintype "passive"))
      (node (ref "U20") (pin "19") (pinfunction "PGND_19") (pintype "passive"))
      (node (ref "U20") (pin "20") (pinfunction "PGND_20") (pintype "passive"))
      (node (ref "U20") (pin "21") (pinfunction "PGND_21") (pintype "passive"))
      (node (ref "U20") (pin "22") (pinfunction "PGND_22") (pintype "passive"))
      (node (ref "U20") (pin "23") (pinfunction "PGND_23") (pintype "passive"))
      (node (ref "U20") (pin "24") (pinfunction "PGND_24") (pintype "passive"))
      (node (ref "U20") (pin "25") (pinfunction "PGND_25") (pintype "passive"))
      (node (ref "U20") (pin "26") (pinfunction "PGND_26") (pintype "passive"))
      (node (ref "U20") (pin "27") (pinfunction "PGND_27") (pintype "passive"))
      (node (ref "U20") (pin "28") (pinfunction "PGND_28") (pintype "passive"))
      (node (ref "U20") (pin "37") (pinfunction "CGND_37") (pintype "passive"))
      (node (ref "U20") (pin "41") (pinfunction "CGND_41") (pintype "passive"))
      (node (ref "U20") (pin "5") (pinfunction "CGND_5") (pintype "passive"))
      (node (ref "U24") (pin "16") (pinfunction "PGND_16") (pintype "passive"))
      (node (ref "U24") (pin "17") (pinfunction "PGND_17") (pintype "passive"))
      (node (ref "U24") (pin "18") (pinfunction "PGND_18") (pintype "passive"))
      (node (ref "U24") (pin "19") (pinfunction "PGND_19") (pintype "passive"))
      (node (ref "U24") (pin "20") (pinfunction "PGND_20") (pintype "passive"))
      (node (ref "U24") (pin "21") (pinfunction "PGND_21") (pintype "passive"))
      (node (ref "U24") (pin "22") (pinfunction "PGND_22") (pintype "passive"))
      (node (ref "U24") (pin "23") (pinfunction "PGND_23") (pintype "passive"))
      (node (ref "U24") (pin "24") (pinfunction "PGND_24") (pintype "passive"))
      (node (ref "U24") (pin "25") (pinfunction "PGND_25") (pintype "passive"))
      (node (ref "U24") (pin "26") (pinfunction "PGND_26") (pintype "passive"))
      (node (ref "U24") (pin "27") (pinfunction "PGND_27") (pintype "passive"))
      (node (ref "U24") (pin "28") (pinfunction "PGND_28") (pintype "passive"))
      (node (ref "U24") (pin "37") (pinfunction "CGND_37") (pintype "passive"))
      (node (ref "U24") (pin "41") (pinfunction "CGND_41") (pintype "passive"))
      (node (ref "U24") (pin "5") (pinfunction "CGND_5") (pintype "passive"))
    )
    (net (code "14") (name "Net-(U13-BOOT)") (class "Default")
      (node (ref "C30") (pin "1") (pinfunction "1_1") (pintype "passive"))
      (node (ref "U13") (pin "4") (pinfunction "BOOT_4") (pintype "passive"))
    )
    (net (code "15") (name "Net-(U13-DSBL#)") (class "Default")
      (node (ref "R15") (pin "1") (pinfunction "1_1") (pintype "passive"))
      (node (ref "U13") (pin "39") (pinfunction "DSBL#_39") (pintype "passive"))
    )
    (net (code "16") (name "Net-(U13-GH)") (class "Default")
      (node (ref "TP8") (pin "1") (pinfunction "1_1") (pintype "passive"))
      (node (ref "U13") (pin "6") (pinfunction "GH_6") (pintype "passive"))
    )
    (net (code "17") (name "Net-(U13-GL)") (class "Default")
      (node (ref "TP15") (pin "1") (pinfunction "1_1") (pintype "passive"))
      (node (ref "U13") (pin "36") (pinfunction "GL_36") (pintype "passive"))
    )
    (net (code "18") (name "Net-(U13-PHASE)") (class "Default")
      (node (ref "C30") (pin "2") (pinfunction "2_2") (pintype "passive"))
      (node (ref "U13") (pin "7") (pinfunction "PHASE_7") (pintype "passive"))
    )
    (net (code "19") (name "Net-(U13-VCIN)") (class "Default")
      (node (ref "C26") (pin "1") (pinfunction "1_1") (pintype "passive"))
      (node (ref "R16") (pin "2") (pinfunction "2_2") (pintype "passive"))
      (node (ref "U13") (pin "2") (pinfunction "VCIN_2") (pintype "passive"))
    )
    (net (code "20") (name "Net-(U17-BOOT)") (class "Default")
      (node (ref "C257") (pin "1") (pinfunction "1_1") (pintype "passive"))
      (node (ref "U17") (pin "4") (pinfunction "BOOT_4") (pintype "passive"))
    )
    (net (code "21") (name "Net-(U17-DSBL#)") (class "Default")
      (node (ref "R23") (pin "1") (pinfunction "1_1") (pintype "passive"))
      (node (ref "U17") (pin "39") (pinfunction "DSBL#_39") (pintype "passive"))
    )
    (net (code "22") (name "Net-(U17-GH)") (class "Default")
      (node (ref "TP17") (pin "1") (pinfunction "1_1") (pintype "passive"))
      (node (ref "U17") (pin "6") (pinfunction "GH_6") (pintype "passive"))
    )
    (net (code "23") (name "Net-(U17-GL)") (class "Default")
      (node (ref "TP27") (pin "1") (pinfunction "1_1") (pintype "passive"))
      (node (ref "U17") (pin "36") (pinfunction "GL_36") (pintype "passive"))
    )
    (net (code "24") (name "Net-(U17-PHASE)") (class "Default")
      (node (ref "C257") (pin "2") (pinfunction "2_2") (pintype "passive"))
      (node (ref "U17") (pin "7") (pinfunction "PHASE_7") (pintype "passive"))
    )
    (net (code "25") (name "Net-(U17-VCIN)") (class "Default")
      (node (ref "C58") (pin "1") (pinfunction "1_1") (pintype "passive"))
      (node (ref "R24") (pin "2") (pinfunction "2_2") (pintype "passive"))
      (node (ref "U17") (pin "2") (pinfunction "VCIN_2") (pintype "passive"))
    )
    (net (code "26") (name "Net-(U20-BOOT)") (class "Default")
      (node (ref "C93") (pin "1") (pinfunction "1_1") (pintype "passive"))
      (node (ref "U20") (pin "4") (pinfunction "BOOT_4") (pintype "passive"))
    )
    (net (code "27") (name "Net-(U20-DSBL#)") (class "Default")
      (node (ref "R2") (pin "1") (pinfunction "1_1") (pintype "passive"))
      (node (ref "U20") (pin "39") (pinfunction "DSBL#_39") (pintype "passive"))
    )
    (net (code "28") (name "Net-(U20-GH)") (class "Default")
      (node (ref "TP4") (pin "1") (pinfunction "1_1") (pintype "passive"))
      (node (ref "U20") (pin "6") (pinfunction "GH_6") (pintype "passive"))
    )
    (net (code "29") (name "Net-(U20-GL)") (class "Default")
      (node (ref "TP9") (pin "1") (pinfunction "1_1") (pintype "passive"))
      (node (ref "U20") (pin "36") (pinfunction "GL_36") (pintype "passive"))
    )
    (net (code "30") (name "Net-(U20-PHASE)") (class "Default")
      (node (ref "C93") (pin "2") (pinfunction "2_2") (pintype "passive"))
      (node (ref "U20") (pin "7") (pinfunction "PHASE_7") (pintype "passive"))
    )
    (net (code "31") (name "Net-(U20-VCIN)") (class "Default")
      (node (ref "C89") (pin "1") (pinfunction "1_1") (pintype "passive"))
      (node (ref "R3") (pin "2") (pinfunction "2_2") (pintype "passive"))
      (node (ref "U20") (pin "2") (pinfunction "VCIN_2") (pintype "passive"))
    )
    (net (code "32") (name "Net-(U24-BOOT)") (class "Default")
      (node (ref "C125") (pin "1") (pinfunction "1_1") (pintype "passive"))
      (node (ref "U24") (pin "4") (pinfunction "BOOT_4") (pintype "passive"))
    )
    (net (code "33") (name "Net-(U24-DSBL#)") (class "Default")
      (node (ref "R17") (pin "1") (pinfunction "1_1") (pintype "passive"))
      (node (ref "U24") (pin "39") (pinfunction "DSBL#_39") (pintype "passive"))
    )
    (net (code "34") (name "Net-(U24-GH)") (class "Default")
      (node (ref "TP16") (pin "1") (pinfunction "1_1") (pintype "passive"))
      (node (ref "U24") (pin "6") (pinfunction "GH_6") (pintype "passive"))
    )
    (net (code "35") (name "Net-(U24-GL)") (class "Default")
      (node (ref "TP26") (pin "1") (pinfunction "1_1") (pintype "passive"))
      (node (ref "U24") (pin "36") (pinfunction "GL_36") (pintype "passive"))
    )
    (net (code "36") (name "Net-(U24-PHASE)") (class "Default")
      (node (ref "C125") (pin "2") (pinfunction "2_2") (pintype "passive"))
      (node (ref "U24") (pin "7") (pinfunction "PHASE_7") (pintype "passive"))
    )
    (net (code "37") (name "Net-(U24-VCIN)") (class "Default")
      (node (ref "C121") (pin "1") (pinfunction "1_1") (pintype "passive"))
      (node (ref "R19") (pin "2") (pinfunction "2_2") (pintype "passive"))
      (node (ref "U24") (pin "2") (pinfunction "VCIN_2") (pintype "passive"))
    )
    (net (code "38") (name "unconnected-(U13-SMOD#-Pad1)") (class "Default")
      (node (ref "U13") (pin "1") (pinfunction "SMOD#_1") (pintype "passive+no_connect"))
    )
    (net (code "39") (name "unconnected-(U17-SMOD#-Pad1)") (class "Default")
      (node (ref "U17") (pin "1") (pinfunction "SMOD#_1") (pintype "passive+no_connect"))
    )
    (net (code "40") (name "unconnected-(U20-SMOD#-Pad1)") (class "Default")
      (node (ref "U20") (pin "1") (pinfunction "SMOD#_1") (pintype "passive+no_connect"))
    )
    (net (code "41") (name "unconnected-(U24-SMOD#-Pad1)") (class "Default")
      (node (ref "U24") (pin "1") (pinfunction "SMOD#_1") (pintype "passive+no_connect"))
    )
  )
)
